# StairLed.net
KiCad netlist of a schematic drawn in Altium Designer
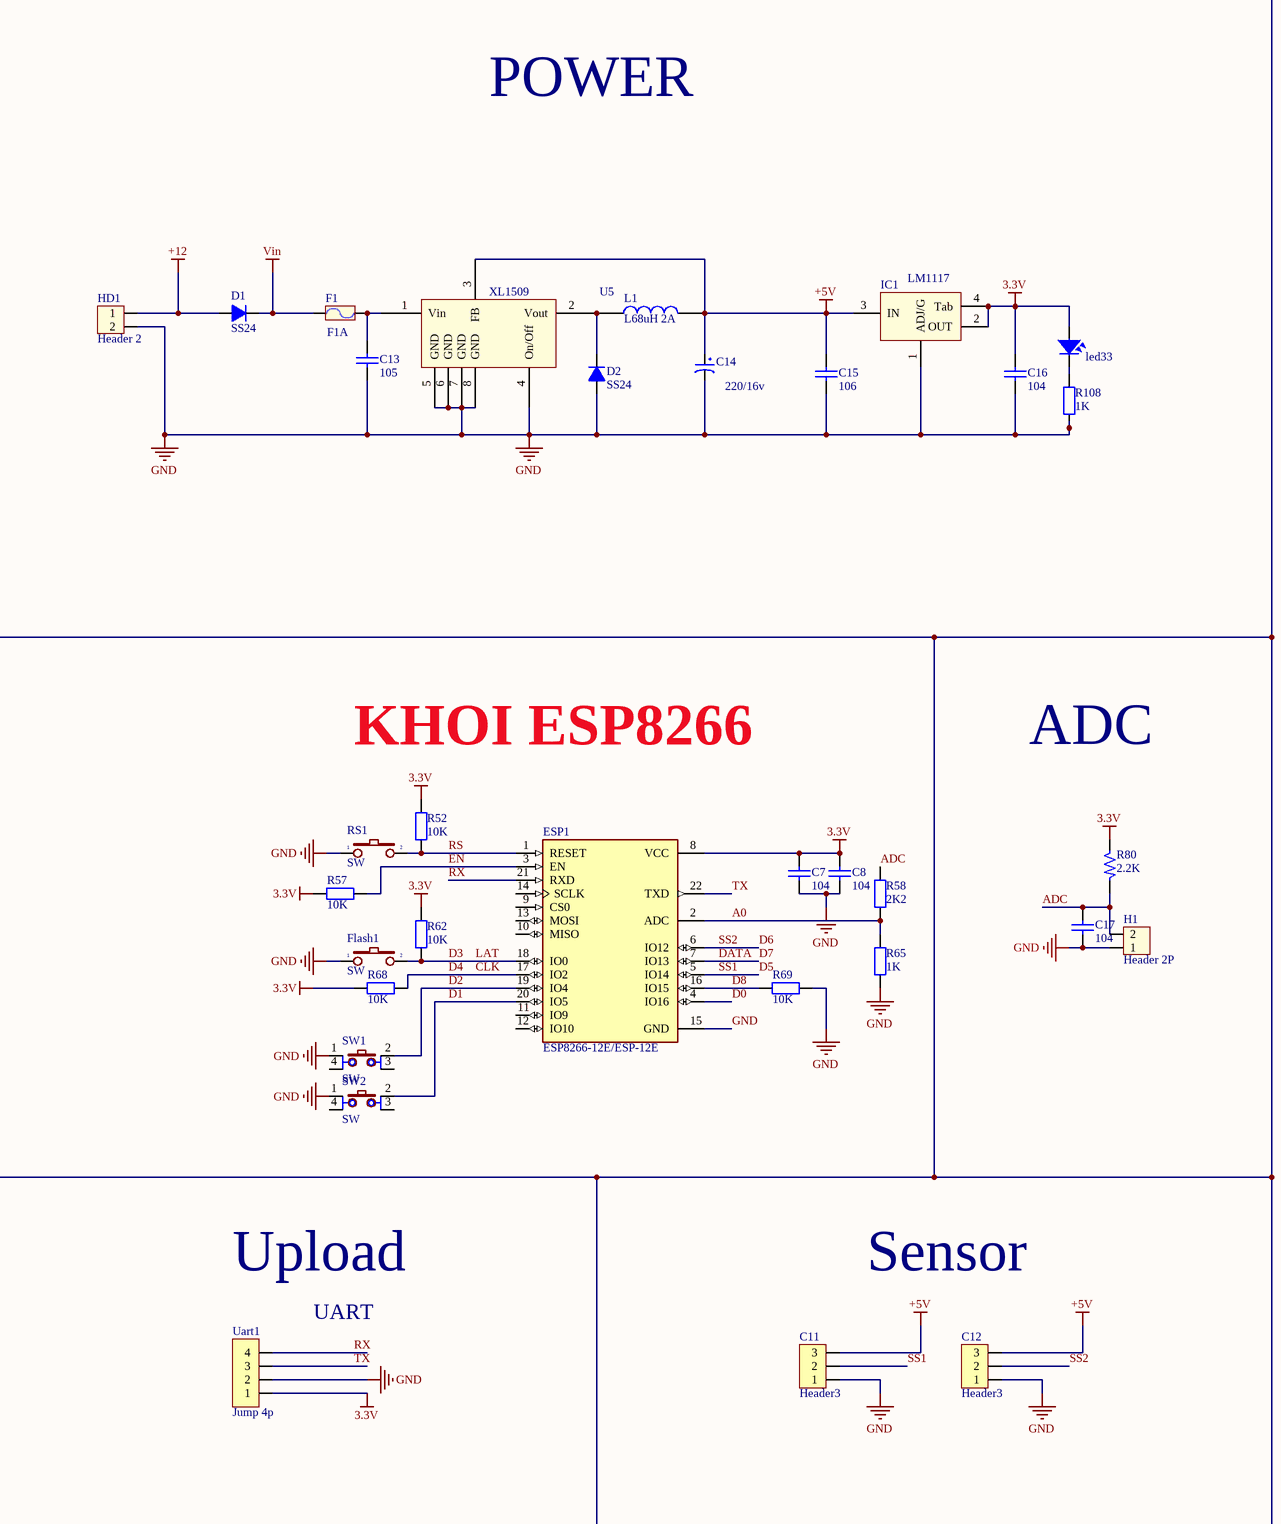
[diagram p0: StairLed.SchDoc, left]
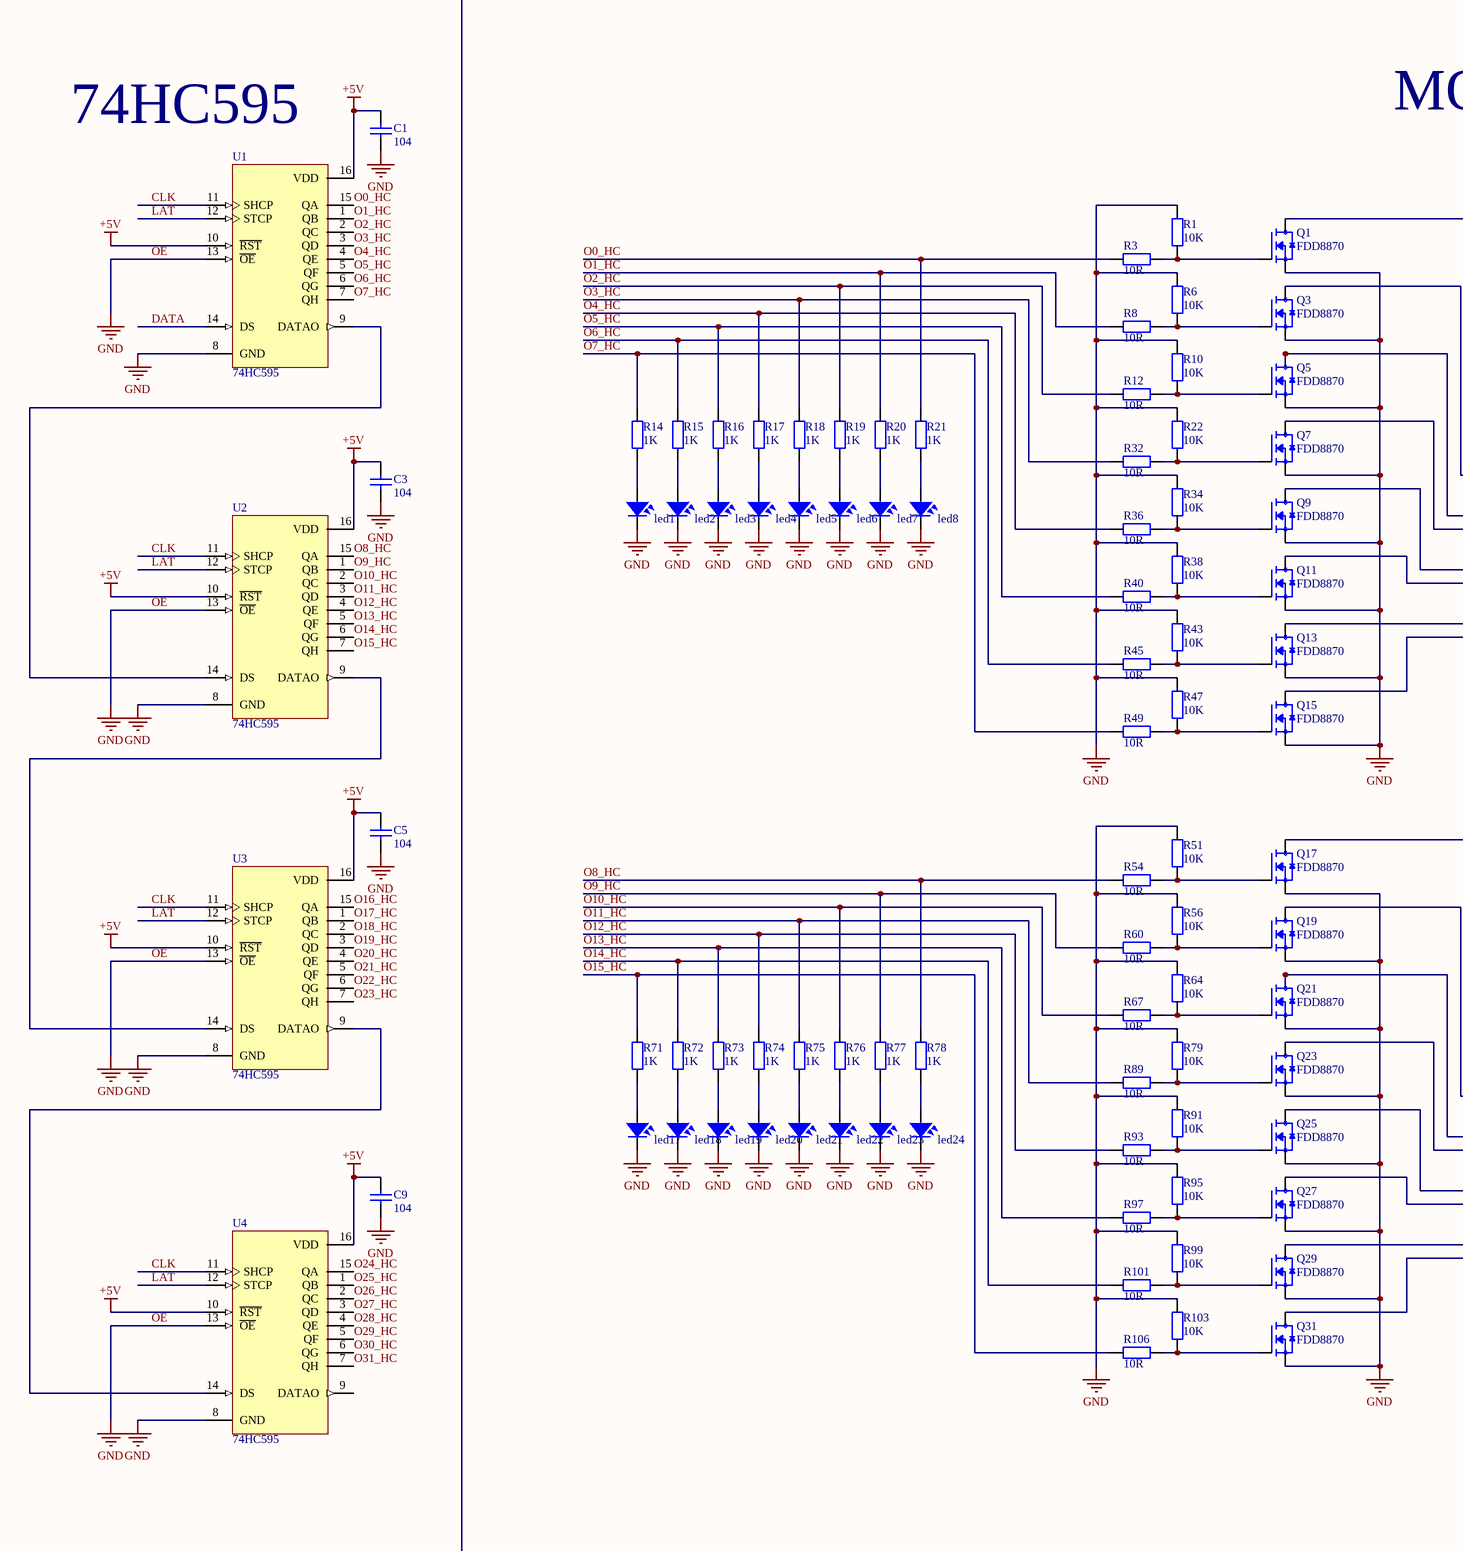
[diagram p1: StairLed.SchDoc, middle]
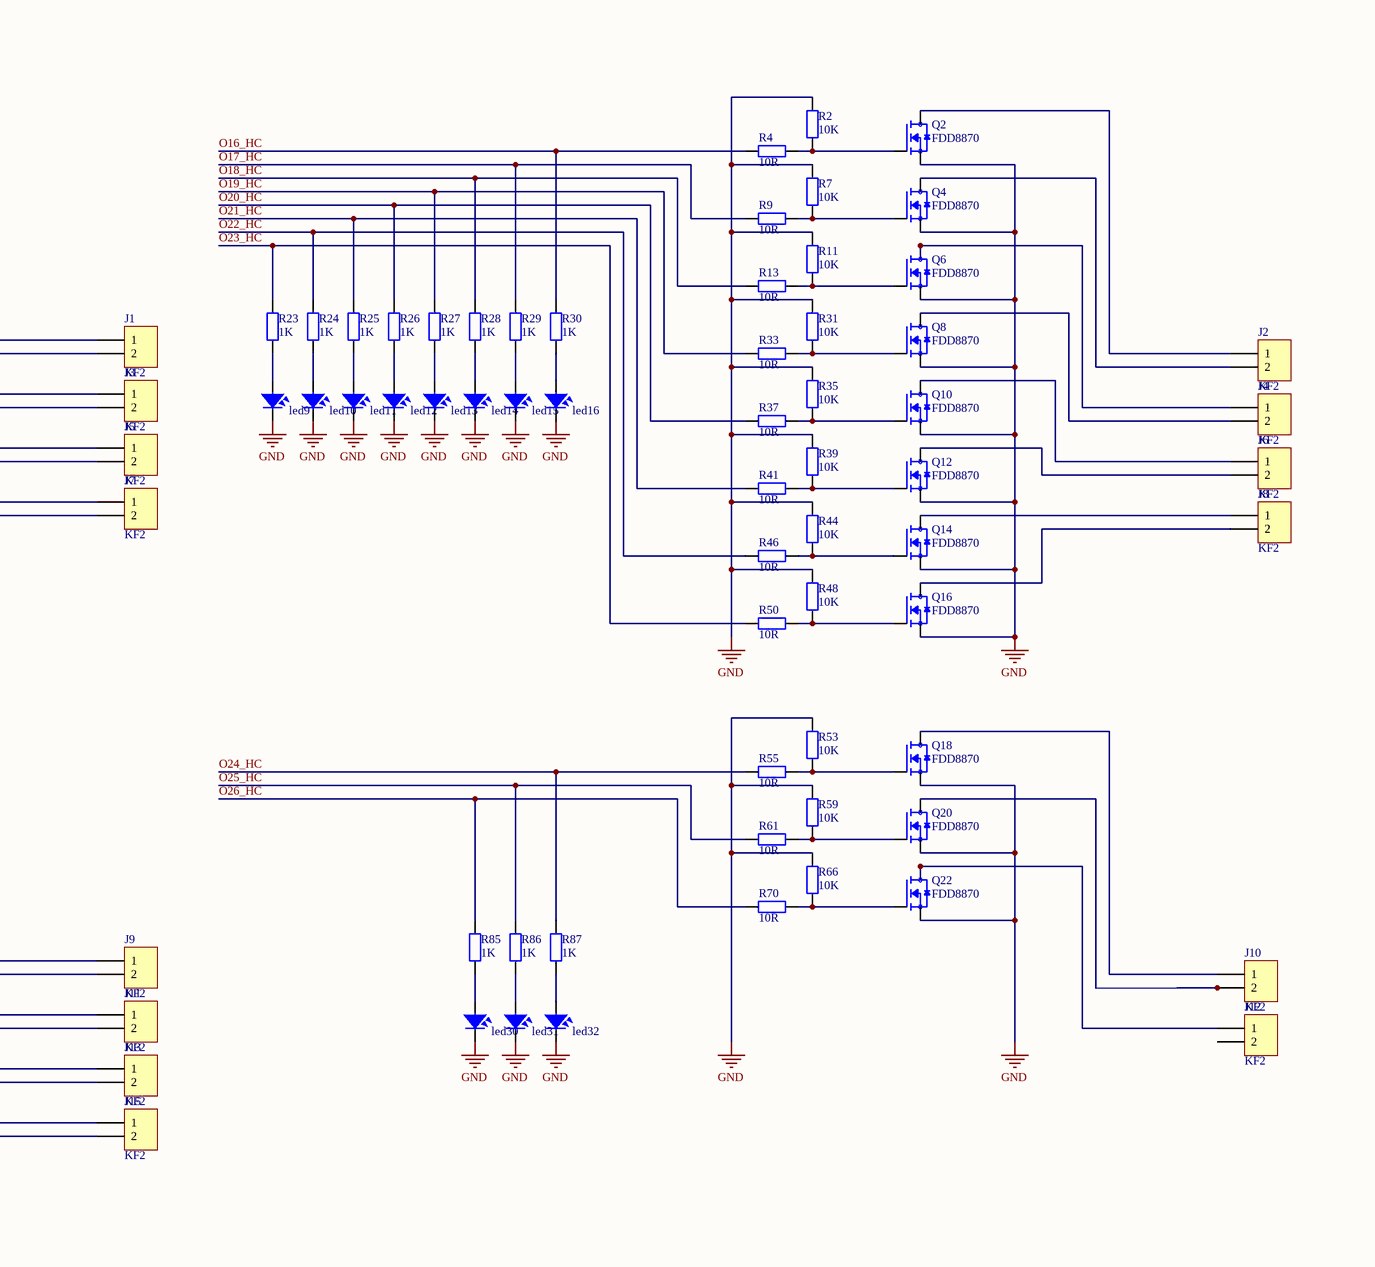
[diagram p2: StairLed.SchDoc, right]

(export (version "E")
  (design (tool "Eeschema 10.0.6"))
  (components
    (comp (ref "C1")
      (value "104")
      (footprint "Cap-0805")
      (libsource (lib "TDX_Local_LIbrary") (part "Cap-0805"))
    )
    (comp (ref "C3")
      (value "104")
      (footprint "Cap-0805")
      (libsource (lib "TDX_Local_LIbrary") (part "Cap-0805"))
    )
    (comp (ref "C5")
      (value "104")
      (footprint "Cap-0805")
      (libsource (lib "TDX_Local_LIbrary") (part "Cap-0805"))
    )
    (comp (ref "C7")
      (value "104")
      (footprint "Cap-0805")
      (description "Capacitor")
      (fields (field (name "PUBLISHER") "Altium Limited"))
      (libsource (lib "*") (part "Cap"))
    )
    (comp (ref "C8")
      (value "104")
      (footprint "Cap-0805")
      (description "Capacitor")
      (fields (field (name "PUBLISHER") "Altium Limited"))
      (libsource (lib "*") (part "Cap"))
    )
    (comp (ref "C9")
      (value "104")
      (footprint "Cap-0805")
      (libsource (lib "TDX_Local_LIbrary") (part "Cap-0805"))
    )
    (comp (ref "C11")
      (value "Header3")
      (footprint "Header3")
      (description "Header IDC, 3 x 1 Pin Vertical 2.54mm Pitch (Non-Boxed, Male)")
      (fields
        (field (name "MANUFACTURER") "Würth Elektronik eiSos GmbH")
        (field (name "PARTNO") "613002143121")
        (field (name "CREATED BY") "Karrer Zheng")
      )
      (libsource (lib "TechMT.VN_Lib_Project v2") (part "Header3"))
    )
    (comp (ref "C12")
      (value "Header3")
      (footprint "Header3")
      (description "Header IDC, 3 x 1 Pin Vertical 2.54mm Pitch (Non-Boxed, Male)")
      (fields
        (field (name "MANUFACTURER") "Würth Elektronik eiSos GmbH")
        (field (name "PARTNO") "613002143121")
        (field (name "CREATED BY") "Karrer Zheng")
      )
      (libsource (lib "TechMT.VN_Lib_Project v2") (part "Header3"))
    )
    (comp (ref "C13")
      (value "105")
      (footprint "Cap-0805")
      (description "Capacitor")
      (fields (field (name "PUBLISHER") "Altium Limited"))
      (libsource (lib "*") (part "Cap"))
    )
    (comp (ref "C14")
      (value "220/16v")
      (footprint "CAP-ALU-SMD-6.3x7.7x2.2")
      (description "T? Nhôm 330uF 50V 10x10.5MM")
      (libsource (lib "thuvien") (part "CP4"))
    )
    (comp (ref "C15")
      (value "106")
      (footprint "Cap-0805")
      (description "Capacitor")
      (fields (field (name "PUBLISHER") "Altium Limited"))
      (libsource (lib "*") (part "Cap"))
    )
    (comp (ref "C16")
      (value "104")
      (footprint "Cap-0805")
      (description "Capacitor")
      (fields (field (name "PUBLISHER") "Altium Limited"))
      (libsource (lib "*") (part "Cap"))
    )
    (comp (ref "C17")
      (value "104")
      (footprint "Cap-0805")
      (libsource (lib "TDX_Local_LIbrary") (part "Cap-0805"))
    )
    (comp (ref "D1")
      (value "SS24")
      (footprint "DO-214AC-Zenner")
      (description "Diode 1A")
      (libsource (lib "thuvien") (part "D1A"))
    )
    (comp (ref "D2")
      (value "SS24")
      (footprint "DO-214AC-Zenner")
      (description "Diode 1A")
      (libsource (lib "thuvien") (part "D1A"))
    )
    (comp (ref "ESP1")
      (value "ESP8266-12E/ESP-12E")
      (footprint "XCVR_ESP8266-12E/ESP-12E")
      (fields (field (name "MF") "AI-Thinker"))
      (libsource (lib "ESP8266-12E_ESP-12E (1)") (part "ESP8266-12E/ESP-12E"))
    )
    (comp (ref "F1")
      (value "F1A")
      (footprint "1812")
      (description "C?u chì t? ph?c h?i 1812 0.5A 30V MSMD050-30V")
      (fields (field (name "DESIGNED BY") "VanDungEvn"))
      (libsource (lib "syhaunguyen") (part "Fuse"))
    )
    (comp (ref "Flash1")
      (value "SW")
      (footprint "SW1-SMD")
      (description "Switch button 2 pin")
      (libsource (lib "TechMT.VN_Lib_Project v2") (part "SW2"))
    )
    (comp (ref "H1")
      (value "Header 2P")
      (footprint "Header 2P-T")
      (libsource (lib "TDX_Local_LIbrary") (part "Header 2P"))
    )
    (comp (ref "HD1")
      (value "Header 2")
      (footprint "HED2")
      (description "Header 2 (Green)")
      (libsource (lib "My library altium") (part "Header 2"))
    )
    (comp (ref "IC1")
      (value "LM1117")
      (footprint "SOT223-4N")
      (description "AMS1117-3.3V SOT223")
      (libsource (lib "thuvien") (part "LM1117"))
    )
    (comp (ref "J1")
      (value "KF2")
      (footprint "KF2-3.5")
      (fields
        (field (name "MANUFACTURER") "Würth Elektronik eiSos GmbH")
        (field (name "PARTNO") "691103110002")
        (field (name "CREATED BY") "Karrer Zheng")
      )
      (libsource (lib "TechMT.VN_Lib_Project v2") (part "KF2"))
    )
    (comp (ref "J2")
      (value "KF2")
      (footprint "KF2-3.5")
      (fields
        (field (name "MANUFACTURER") "Würth Elektronik eiSos GmbH")
        (field (name "PARTNO") "691103110002")
        (field (name "CREATED BY") "Karrer Zheng")
      )
      (libsource (lib "TechMT.VN_Lib_Project v2") (part "KF2"))
    )
    (comp (ref "J3")
      (value "KF2")
      (footprint "KF2-3.5")
      (fields
        (field (name "MANUFACTURER") "Würth Elektronik eiSos GmbH")
        (field (name "PARTNO") "691103110002")
        (field (name "CREATED BY") "Karrer Zheng")
      )
      (libsource (lib "TechMT.VN_Lib_Project v2") (part "KF2"))
    )
    (comp (ref "J4")
      (value "KF2")
      (footprint "KF2-3.5")
      (fields
        (field (name "MANUFACTURER") "Würth Elektronik eiSos GmbH")
        (field (name "PARTNO") "691103110002")
        (field (name "CREATED BY") "Karrer Zheng")
      )
      (libsource (lib "TechMT.VN_Lib_Project v2") (part "KF2"))
    )
    (comp (ref "J5")
      (value "KF2")
      (footprint "KF2-3.5")
      (fields
        (field (name "MANUFACTURER") "Würth Elektronik eiSos GmbH")
        (field (name "PARTNO") "691103110002")
        (field (name "CREATED BY") "Karrer Zheng")
      )
      (libsource (lib "TechMT.VN_Lib_Project v2") (part "KF2"))
    )
    (comp (ref "J6")
      (value "KF2")
      (footprint "KF2-3.5")
      (fields
        (field (name "MANUFACTURER") "Würth Elektronik eiSos GmbH")
        (field (name "PARTNO") "691103110002")
        (field (name "CREATED BY") "Karrer Zheng")
      )
      (libsource (lib "TechMT.VN_Lib_Project v2") (part "KF2"))
    )
    (comp (ref "J7")
      (value "KF2")
      (footprint "KF2-3.5")
      (fields
        (field (name "MANUFACTURER") "Würth Elektronik eiSos GmbH")
        (field (name "PARTNO") "691103110002")
        (field (name "CREATED BY") "Karrer Zheng")
      )
      (libsource (lib "TechMT.VN_Lib_Project v2") (part "KF2"))
    )
    (comp (ref "J8")
      (value "KF2")
      (footprint "KF2-3.5")
      (fields
        (field (name "MANUFACTURER") "Würth Elektronik eiSos GmbH")
        (field (name "PARTNO") "691103110002")
        (field (name "CREATED BY") "Karrer Zheng")
      )
      (libsource (lib "TechMT.VN_Lib_Project v2") (part "KF2"))
    )
    (comp (ref "J9")
      (value "KF2")
      (footprint "KF2-3.5")
      (fields
        (field (name "MANUFACTURER") "Würth Elektronik eiSos GmbH")
        (field (name "PARTNO") "691103110002")
        (field (name "CREATED BY") "Karrer Zheng")
      )
      (libsource (lib "TechMT.VN_Lib_Project v2") (part "KF2"))
    )
    (comp (ref "J10")
      (value "KF2")
      (footprint "KF2-3.5")
      (fields
        (field (name "MANUFACTURER") "Würth Elektronik eiSos GmbH")
        (field (name "PARTNO") "691103110002")
        (field (name "CREATED BY") "Karrer Zheng")
      )
      (libsource (lib "TechMT.VN_Lib_Project v2") (part "KF2"))
    )
    (comp (ref "J11")
      (value "KF2")
      (footprint "KF2-3.5")
      (fields
        (field (name "MANUFACTURER") "Würth Elektronik eiSos GmbH")
        (field (name "PARTNO") "691103110002")
        (field (name "CREATED BY") "Karrer Zheng")
      )
      (libsource (lib "TechMT.VN_Lib_Project v2") (part "KF2"))
    )
    (comp (ref "J12")
      (value "KF2")
      (footprint "KF2-3.5")
      (fields
        (field (name "MANUFACTURER") "Würth Elektronik eiSos GmbH")
        (field (name "PARTNO") "691103110002")
        (field (name "CREATED BY") "Karrer Zheng")
      )
      (libsource (lib "TechMT.VN_Lib_Project v2") (part "KF2"))
    )
    (comp (ref "J13")
      (value "KF2")
      (footprint "KF2-3.5")
      (fields
        (field (name "MANUFACTURER") "Würth Elektronik eiSos GmbH")
        (field (name "PARTNO") "691103110002")
        (field (name "CREATED BY") "Karrer Zheng")
      )
      (libsource (lib "TechMT.VN_Lib_Project v2") (part "KF2"))
    )
    (comp (ref "J15")
      (value "KF2")
      (footprint "KF2-3.5")
      (fields
        (field (name "MANUFACTURER") "Würth Elektronik eiSos GmbH")
        (field (name "PARTNO") "691103110002")
        (field (name "CREATED BY") "Karrer Zheng")
      )
      (libsource (lib "TechMT.VN_Lib_Project v2") (part "KF2"))
    )
    (comp (ref "L1")
      (value "L68uH 2A")
      (footprint "5D28")
      (description "Cu?n c?m dán CD74 68uH 7.4x7.4x4mm")
      (libsource (lib "*") (part "INDUCTOR"))
    )
    (comp (ref "led1")
      (value "LED SMD")
      (footprint "SM-LED-0805-Blue")
      (libsource (lib "syhaunguyen") (part "LED-SMD-0805"))
    )
    (comp (ref "led2")
      (value "LED SMD")
      (footprint "SM-LED-0805-Blue")
      (libsource (lib "syhaunguyen") (part "LED-SMD-0805"))
    )
    (comp (ref "led3")
      (value "LED SMD")
      (footprint "SM-LED-0805-Blue")
      (libsource (lib "syhaunguyen") (part "LED-SMD-0805"))
    )
    (comp (ref "led4")
      (value "LED SMD")
      (footprint "SM-LED-0805-Blue")
      (libsource (lib "syhaunguyen") (part "LED-SMD-0805"))
    )
    (comp (ref "led5")
      (value "LED SMD")
      (footprint "SM-LED-0805-Blue")
      (libsource (lib "syhaunguyen") (part "LED-SMD-0805"))
    )
    (comp (ref "led6")
      (value "LED SMD")
      (footprint "SM-LED-0805-Blue")
      (libsource (lib "syhaunguyen") (part "LED-SMD-0805"))
    )
    (comp (ref "led7")
      (value "LED SMD")
      (footprint "SM-LED-0805-Blue")
      (libsource (lib "syhaunguyen") (part "LED-SMD-0805"))
    )
    (comp (ref "led8")
      (value "LED SMD")
      (footprint "SM-LED-0805-Blue")
      (libsource (lib "syhaunguyen") (part "LED-SMD-0805"))
    )
    (comp (ref "led9")
      (value "LED SMD")
      (footprint "SM-LED-0805-Blue")
      (libsource (lib "syhaunguyen") (part "LED-SMD-0805"))
    )
    (comp (ref "led10")
      (value "LED SMD")
      (footprint "SM-LED-0805-Blue")
      (libsource (lib "syhaunguyen") (part "LED-SMD-0805"))
    )
    (comp (ref "led11")
      (value "LED SMD")
      (footprint "SM-LED-0805-Blue")
      (libsource (lib "syhaunguyen") (part "LED-SMD-0805"))
    )
    (comp (ref "led12")
      (value "LED SMD")
      (footprint "SM-LED-0805-Blue")
      (libsource (lib "syhaunguyen") (part "LED-SMD-0805"))
    )
    (comp (ref "led13")
      (value "LED SMD")
      (footprint "SM-LED-0805-Blue")
      (libsource (lib "syhaunguyen") (part "LED-SMD-0805"))
    )
    (comp (ref "led14")
      (value "LED SMD")
      (footprint "SM-LED-0805-Blue")
      (libsource (lib "syhaunguyen") (part "LED-SMD-0805"))
    )
    (comp (ref "led15")
      (value "LED SMD")
      (footprint "SM-LED-0805-Blue")
      (libsource (lib "syhaunguyen") (part "LED-SMD-0805"))
    )
    (comp (ref "led16")
      (value "LED SMD")
      (footprint "SM-LED-0805-Blue")
      (libsource (lib "syhaunguyen") (part "LED-SMD-0805"))
    )
    (comp (ref "led17")
      (value "LED SMD")
      (footprint "SM-LED-0805-Blue")
      (libsource (lib "syhaunguyen") (part "LED-SMD-0805"))
    )
    (comp (ref "led18")
      (value "LED SMD")
      (footprint "SM-LED-0805-Blue")
      (libsource (lib "syhaunguyen") (part "LED-SMD-0805"))
    )
    (comp (ref "led19")
      (value "LED SMD")
      (footprint "SM-LED-0805-Blue")
      (libsource (lib "syhaunguyen") (part "LED-SMD-0805"))
    )
    (comp (ref "led20")
      (value "LED SMD")
      (footprint "SM-LED-0805-Blue")
      (libsource (lib "syhaunguyen") (part "LED-SMD-0805"))
    )
    (comp (ref "led21")
      (value "LED SMD")
      (footprint "SM-LED-0805-Blue")
      (libsource (lib "syhaunguyen") (part "LED-SMD-0805"))
    )
    (comp (ref "led22")
      (value "LED SMD")
      (footprint "SM-LED-0805-Blue")
      (libsource (lib "syhaunguyen") (part "LED-SMD-0805"))
    )
    (comp (ref "led23")
      (value "LED SMD")
      (footprint "SM-LED-0805-Blue")
      (libsource (lib "syhaunguyen") (part "LED-SMD-0805"))
    )
    (comp (ref "led24")
      (value "LED SMD")
      (footprint "SM-LED-0805-Blue")
      (libsource (lib "syhaunguyen") (part "LED-SMD-0805"))
    )
    (comp (ref "led30")
      (value "LED SMD")
      (footprint "SM-LED-0805-Blue")
      (libsource (lib "syhaunguyen") (part "LED-SMD-0805"))
    )
    (comp (ref "led31")
      (value "LED SMD")
      (footprint "SM-LED-0805-Blue")
      (libsource (lib "syhaunguyen") (part "LED-SMD-0805"))
    )
    (comp (ref "led32")
      (value "LED SMD")
      (footprint "SM-LED-0805-Blue")
      (libsource (lib "syhaunguyen") (part "LED-SMD-0805"))
    )
    (comp (ref "led33")
      (value "LED SMD")
      (footprint "SM-LED-0805-Blue")
      (libsource (lib "syhaunguyen") (part "LED-SMD-0805"))
    )
    (comp (ref "Q1")
      (value "FDD8870")
      (footprint "TRANS_SQD50N03-06P-GE3")
      (fields (field (name "MP") "SQD50N03-06P-GE3"))
      (libsource (lib "SQD50N03-06P-GE3") (part "SQD50N03-06P-GE3"))
    )
    (comp (ref "Q2")
      (value "FDD8870")
      (footprint "TRANS_SQD50N03-06P-GE3")
      (fields (field (name "MP") "SQD50N03-06P-GE3"))
      (libsource (lib "SQD50N03-06P-GE3") (part "SQD50N03-06P-GE3"))
    )
    (comp (ref "Q3")
      (value "FDD8870")
      (footprint "TRANS_SQD50N03-06P-GE3")
      (fields (field (name "MP") "SQD50N03-06P-GE3"))
      (libsource (lib "SQD50N03-06P-GE3") (part "SQD50N03-06P-GE3"))
    )
    (comp (ref "Q4")
      (value "FDD8870")
      (footprint "TRANS_SQD50N03-06P-GE3")
      (fields (field (name "MP") "SQD50N03-06P-GE3"))
      (libsource (lib "SQD50N03-06P-GE3") (part "SQD50N03-06P-GE3"))
    )
    (comp (ref "Q5")
      (value "FDD8870")
      (footprint "TRANS_SQD50N03-06P-GE3")
      (fields (field (name "MP") "SQD50N03-06P-GE3"))
      (libsource (lib "SQD50N03-06P-GE3") (part "SQD50N03-06P-GE3"))
    )
    (comp (ref "Q6")
      (value "FDD8870")
      (footprint "TRANS_SQD50N03-06P-GE3")
      (fields (field (name "MP") "SQD50N03-06P-GE3"))
      (libsource (lib "SQD50N03-06P-GE3") (part "SQD50N03-06P-GE3"))
    )
    (comp (ref "Q7")
      (value "FDD8870")
      (footprint "TRANS_SQD50N03-06P-GE3")
      (fields (field (name "MP") "SQD50N03-06P-GE3"))
      (libsource (lib "SQD50N03-06P-GE3") (part "SQD50N03-06P-GE3"))
    )
    (comp (ref "Q8")
      (value "FDD8870")
      (footprint "TRANS_SQD50N03-06P-GE3")
      (fields (field (name "MP") "SQD50N03-06P-GE3"))
      (libsource (lib "SQD50N03-06P-GE3") (part "SQD50N03-06P-GE3"))
    )
    (comp (ref "Q9")
      (value "FDD8870")
      (footprint "TRANS_SQD50N03-06P-GE3")
      (fields (field (name "MP") "SQD50N03-06P-GE3"))
      (libsource (lib "SQD50N03-06P-GE3") (part "SQD50N03-06P-GE3"))
    )
    (comp (ref "Q10")
      (value "FDD8870")
      (footprint "TRANS_SQD50N03-06P-GE3")
      (fields (field (name "MP") "SQD50N03-06P-GE3"))
      (libsource (lib "SQD50N03-06P-GE3") (part "SQD50N03-06P-GE3"))
    )
    (comp (ref "Q11")
      (value "FDD8870")
      (footprint "TRANS_SQD50N03-06P-GE3")
      (fields (field (name "MP") "SQD50N03-06P-GE3"))
      (libsource (lib "SQD50N03-06P-GE3") (part "SQD50N03-06P-GE3"))
    )
    (comp (ref "Q12")
      (value "FDD8870")
      (footprint "TRANS_SQD50N03-06P-GE3")
      (fields (field (name "MP") "SQD50N03-06P-GE3"))
      (libsource (lib "SQD50N03-06P-GE3") (part "SQD50N03-06P-GE3"))
    )
    (comp (ref "Q13")
      (value "FDD8870")
      (footprint "TRANS_SQD50N03-06P-GE3")
      (fields (field (name "MP") "SQD50N03-06P-GE3"))
      (libsource (lib "SQD50N03-06P-GE3") (part "SQD50N03-06P-GE3"))
    )
    (comp (ref "Q14")
      (value "FDD8870")
      (footprint "TRANS_SQD50N03-06P-GE3")
      (fields (field (name "MP") "SQD50N03-06P-GE3"))
      (libsource (lib "SQD50N03-06P-GE3") (part "SQD50N03-06P-GE3"))
    )
    (comp (ref "Q15")
      (value "FDD8870")
      (footprint "TRANS_SQD50N03-06P-GE3")
      (fields (field (name "MP") "SQD50N03-06P-GE3"))
      (libsource (lib "SQD50N03-06P-GE3") (part "SQD50N03-06P-GE3"))
    )
    (comp (ref "Q16")
      (value "FDD8870")
      (footprint "TRANS_SQD50N03-06P-GE3")
      (fields (field (name "MP") "SQD50N03-06P-GE3"))
      (libsource (lib "SQD50N03-06P-GE3") (part "SQD50N03-06P-GE3"))
    )
    (comp (ref "Q17")
      (value "FDD8870")
      (footprint "TRANS_SQD50N03-06P-GE3")
      (fields (field (name "MP") "SQD50N03-06P-GE3"))
      (libsource (lib "SQD50N03-06P-GE3") (part "SQD50N03-06P-GE3"))
    )
    (comp (ref "Q18")
      (value "FDD8870")
      (footprint "TRANS_SQD50N03-06P-GE3")
      (fields (field (name "MP") "SQD50N03-06P-GE3"))
      (libsource (lib "SQD50N03-06P-GE3") (part "SQD50N03-06P-GE3"))
    )
    (comp (ref "Q19")
      (value "FDD8870")
      (footprint "TRANS_SQD50N03-06P-GE3")
      (fields (field (name "MP") "SQD50N03-06P-GE3"))
      (libsource (lib "SQD50N03-06P-GE3") (part "SQD50N03-06P-GE3"))
    )
    (comp (ref "Q20")
      (value "FDD8870")
      (footprint "TRANS_SQD50N03-06P-GE3")
      (fields (field (name "MP") "SQD50N03-06P-GE3"))
      (libsource (lib "SQD50N03-06P-GE3") (part "SQD50N03-06P-GE3"))
    )
    (comp (ref "Q21")
      (value "FDD8870")
      (footprint "TRANS_SQD50N03-06P-GE3")
      (fields (field (name "MP") "SQD50N03-06P-GE3"))
      (libsource (lib "SQD50N03-06P-GE3") (part "SQD50N03-06P-GE3"))
    )
    (comp (ref "Q22")
      (value "FDD8870")
      (footprint "TRANS_SQD50N03-06P-GE3")
      (fields (field (name "MP") "SQD50N03-06P-GE3"))
      (libsource (lib "SQD50N03-06P-GE3") (part "SQD50N03-06P-GE3"))
    )
    (comp (ref "Q23")
      (value "FDD8870")
      (footprint "TRANS_SQD50N03-06P-GE3")
      (fields (field (name "MP") "SQD50N03-06P-GE3"))
      (libsource (lib "SQD50N03-06P-GE3") (part "SQD50N03-06P-GE3"))
    )
    (comp (ref "Q25")
      (value "FDD8870")
      (footprint "TRANS_SQD50N03-06P-GE3")
      (fields (field (name "MP") "SQD50N03-06P-GE3"))
      (libsource (lib "SQD50N03-06P-GE3") (part "SQD50N03-06P-GE3"))
    )
    (comp (ref "Q27")
      (value "FDD8870")
      (footprint "TRANS_SQD50N03-06P-GE3")
      (fields (field (name "MP") "SQD50N03-06P-GE3"))
      (libsource (lib "SQD50N03-06P-GE3") (part "SQD50N03-06P-GE3"))
    )
    (comp (ref "Q29")
      (value "FDD8870")
      (footprint "TRANS_SQD50N03-06P-GE3")
      (fields (field (name "MP") "SQD50N03-06P-GE3"))
      (libsource (lib "SQD50N03-06P-GE3") (part "SQD50N03-06P-GE3"))
    )
    (comp (ref "Q31")
      (value "FDD8870")
      (footprint "TRANS_SQD50N03-06P-GE3")
      (fields (field (name "MP") "SQD50N03-06P-GE3"))
      (libsource (lib "SQD50N03-06P-GE3") (part "SQD50N03-06P-GE3"))
    )
    (comp (ref "R1")
      (value "10K")
      (footprint "R0805")
      (description "Tr? 0805 1%")
      (fields (field (name "PUBLISHER") "Altium Limited"))
      (libsource (lib "") (part "RES_08_2"))
    )
    (comp (ref "R2")
      (value "10K")
      (footprint "R0805")
      (description "Tr? 0805 1%")
      (fields (field (name "PUBLISHER") "Altium Limited"))
      (libsource (lib "") (part "RES_08_2"))
    )
    (comp (ref "R3")
      (value "10R")
      (footprint "R0805")
      (description "Tr? 0805 1%")
      (fields (field (name "PUBLISHER") "Altium Limited"))
      (libsource (lib "Schematic") (part "RES_08"))
    )
    (comp (ref "R4")
      (value "10R")
      (footprint "R0805")
      (description "Tr? 0805 1%")
      (fields (field (name "PUBLISHER") "Altium Limited"))
      (libsource (lib "Schematic") (part "RES_08"))
    )
    (comp (ref "R6")
      (value "10K")
      (footprint "R0805")
      (description "Tr? 0805 1%")
      (fields (field (name "PUBLISHER") "Altium Limited"))
      (libsource (lib "") (part "RES_08_2"))
    )
    (comp (ref "R7")
      (value "10K")
      (footprint "R0805")
      (description "Tr? 0805 1%")
      (fields (field (name "PUBLISHER") "Altium Limited"))
      (libsource (lib "") (part "RES_08_2"))
    )
    (comp (ref "R8")
      (value "10R")
      (footprint "R0805")
      (description "Tr? 0805 1%")
      (fields (field (name "PUBLISHER") "Altium Limited"))
      (libsource (lib "Schematic") (part "RES_08"))
    )
    (comp (ref "R9")
      (value "10R")
      (footprint "R0805")
      (description "Tr? 0805 1%")
      (fields (field (name "PUBLISHER") "Altium Limited"))
      (libsource (lib "Schematic") (part "RES_08"))
    )
    (comp (ref "R10")
      (value "10K")
      (footprint "R0805")
      (description "Tr? 0805 1%")
      (fields (field (name "PUBLISHER") "Altium Limited"))
      (libsource (lib "") (part "RES_08_2"))
    )
    (comp (ref "R11")
      (value "10K")
      (footprint "R0805")
      (description "Tr? 0805 1%")
      (fields (field (name "PUBLISHER") "Altium Limited"))
      (libsource (lib "") (part "RES_08_2"))
    )
    (comp (ref "R12")
      (value "10R")
      (footprint "R0805")
      (description "Tr? 0805 1%")
      (fields (field (name "PUBLISHER") "Altium Limited"))
      (libsource (lib "Schematic") (part "RES_08"))
    )
    (comp (ref "R13")
      (value "10R")
      (footprint "R0805")
      (description "Tr? 0805 1%")
      (fields (field (name "PUBLISHER") "Altium Limited"))
      (libsource (lib "Schematic") (part "RES_08"))
    )
    (comp (ref "R14")
      (value "1K")
      (footprint "R0805")
      (description "Tr? 0805 1%")
      (fields (field (name "PUBLISHER") "Altium Limited"))
      (libsource (lib "") (part "RES_08_1"))
    )
    (comp (ref "R15")
      (value "1K")
      (footprint "R0805")
      (description "Tr? 0805 1%")
      (fields (field (name "PUBLISHER") "Altium Limited"))
      (libsource (lib "") (part "RES_08_1"))
    )
    (comp (ref "R16")
      (value "1K")
      (footprint "R0805")
      (description "Tr? 0805 1%")
      (fields (field (name "PUBLISHER") "Altium Limited"))
      (libsource (lib "") (part "RES_08_1"))
    )
    (comp (ref "R17")
      (value "1K")
      (footprint "R0805")
      (description "Tr? 0805 1%")
      (fields (field (name "PUBLISHER") "Altium Limited"))
      (libsource (lib "") (part "RES_08_1"))
    )
    (comp (ref "R18")
      (value "1K")
      (footprint "R0805")
      (description "Tr? 0805 1%")
      (fields (field (name "PUBLISHER") "Altium Limited"))
      (libsource (lib "") (part "RES_08_1"))
    )
    (comp (ref "R19")
      (value "1K")
      (footprint "R0805")
      (description "Tr? 0805 1%")
      (fields (field (name "PUBLISHER") "Altium Limited"))
      (libsource (lib "") (part "RES_08_1"))
    )
    (comp (ref "R20")
      (value "1K")
      (footprint "R0805")
      (description "Tr? 0805 1%")
      (fields (field (name "PUBLISHER") "Altium Limited"))
      (libsource (lib "") (part "RES_08_1"))
    )
    (comp (ref "R21")
      (value "1K")
      (footprint "R0805")
      (description "Tr? 0805 1%")
      (fields (field (name "PUBLISHER") "Altium Limited"))
      (libsource (lib "") (part "RES_08_1"))
    )
    (comp (ref "R22")
      (value "10K")
      (footprint "R0805")
      (description "Tr? 0805 1%")
      (fields (field (name "PUBLISHER") "Altium Limited"))
      (libsource (lib "") (part "RES_08_2"))
    )
    (comp (ref "R23")
      (value "1K")
      (footprint "R0805")
      (description "Tr? 0805 1%")
      (fields (field (name "PUBLISHER") "Altium Limited"))
      (libsource (lib "") (part "RES_08_1"))
    )
    (comp (ref "R24")
      (value "1K")
      (footprint "R0805")
      (description "Tr? 0805 1%")
      (fields (field (name "PUBLISHER") "Altium Limited"))
      (libsource (lib "") (part "RES_08_1"))
    )
    (comp (ref "R25")
      (value "1K")
      (footprint "R0805")
      (description "Tr? 0805 1%")
      (fields (field (name "PUBLISHER") "Altium Limited"))
      (libsource (lib "") (part "RES_08_1"))
    )
    (comp (ref "R26")
      (value "1K")
      (footprint "R0805")
      (description "Tr? 0805 1%")
      (fields (field (name "PUBLISHER") "Altium Limited"))
      (libsource (lib "") (part "RES_08_1"))
    )
    (comp (ref "R27")
      (value "1K")
      (footprint "R0805")
      (description "Tr? 0805 1%")
      (fields (field (name "PUBLISHER") "Altium Limited"))
      (libsource (lib "") (part "RES_08_1"))
    )
    (comp (ref "R28")
      (value "1K")
      (footprint "R0805")
      (description "Tr? 0805 1%")
      (fields (field (name "PUBLISHER") "Altium Limited"))
      (libsource (lib "") (part "RES_08_1"))
    )
    (comp (ref "R29")
      (value "1K")
      (footprint "R0805")
      (description "Tr? 0805 1%")
      (fields (field (name "PUBLISHER") "Altium Limited"))
      (libsource (lib "") (part "RES_08_1"))
    )
    (comp (ref "R30")
      (value "1K")
      (footprint "R0805")
      (description "Tr? 0805 1%")
      (fields (field (name "PUBLISHER") "Altium Limited"))
      (libsource (lib "") (part "RES_08_1"))
    )
    (comp (ref "R31")
      (value "10K")
      (footprint "R0805")
      (description "Tr? 0805 1%")
      (fields (field (name "PUBLISHER") "Altium Limited"))
      (libsource (lib "") (part "RES_08_2"))
    )
    (comp (ref "R32")
      (value "10R")
      (footprint "R0805")
      (description "Tr? 0805 1%")
      (fields (field (name "PUBLISHER") "Altium Limited"))
      (libsource (lib "Schematic") (part "RES_08"))
    )
    (comp (ref "R33")
      (value "10R")
      (footprint "R0805")
      (description "Tr? 0805 1%")
      (fields (field (name "PUBLISHER") "Altium Limited"))
      (libsource (lib "Schematic") (part "RES_08"))
    )
    (comp (ref "R34")
      (value "10K")
      (footprint "R0805")
      (description "Tr? 0805 1%")
      (fields (field (name "PUBLISHER") "Altium Limited"))
      (libsource (lib "") (part "RES_08_2"))
    )
    (comp (ref "R35")
      (value "10K")
      (footprint "R0805")
      (description "Tr? 0805 1%")
      (fields (field (name "PUBLISHER") "Altium Limited"))
      (libsource (lib "") (part "RES_08_2"))
    )
    (comp (ref "R36")
      (value "10R")
      (footprint "R0805")
      (description "Tr? 0805 1%")
      (fields (field (name "PUBLISHER") "Altium Limited"))
      (libsource (lib "Schematic") (part "RES_08"))
    )
    (comp (ref "R37")
      (value "10R")
      (footprint "R0805")
      (description "Tr? 0805 1%")
      (fields (field (name "PUBLISHER") "Altium Limited"))
      (libsource (lib "Schematic") (part "RES_08"))
    )
    (comp (ref "R38")
      (value "10K")
      (footprint "R0805")
      (description "Tr? 0805 1%")
      (fields (field (name "PUBLISHER") "Altium Limited"))
      (libsource (lib "") (part "RES_08_2"))
    )
    (comp (ref "R39")
      (value "10K")
      (footprint "R0805")
      (description "Tr? 0805 1%")
      (fields (field (name "PUBLISHER") "Altium Limited"))
      (libsource (lib "") (part "RES_08_2"))
    )
    (comp (ref "R40")
      (value "10R")
      (footprint "R0805")
      (description "Tr? 0805 1%")
      (fields (field (name "PUBLISHER") "Altium Limited"))
      (libsource (lib "Schematic") (part "RES_08"))
    )
    (comp (ref "R41")
      (value "10R")
      (footprint "R0805")
      (description "Tr? 0805 1%")
      (fields (field (name "PUBLISHER") "Altium Limited"))
      (libsource (lib "Schematic") (part "RES_08"))
    )
    (comp (ref "R43")
      (value "10K")
      (footprint "R0805")
      (description "Tr? 0805 1%")
      (fields (field (name "PUBLISHER") "Altium Limited"))
      (libsource (lib "") (part "RES_08_2"))
    )
    (comp (ref "R44")
      (value "10K")
      (footprint "R0805")
      (description "Tr? 0805 1%")
      (fields (field (name "PUBLISHER") "Altium Limited"))
      (libsource (lib "") (part "RES_08_2"))
    )
    (comp (ref "R45")
      (value "10R")
      (footprint "R0805")
      (description "Tr? 0805 1%")
      (fields (field (name "PUBLISHER") "Altium Limited"))
      (libsource (lib "Schematic") (part "RES_08"))
    )
    (comp (ref "R46")
      (value "10R")
      (footprint "R0805")
      (description "Tr? 0805 1%")
      (fields (field (name "PUBLISHER") "Altium Limited"))
      (libsource (lib "Schematic") (part "RES_08"))
    )
    (comp (ref "R47")
      (value "10K")
      (footprint "R0805")
      (description "Tr? 0805 1%")
      (fields (field (name "PUBLISHER") "Altium Limited"))
      (libsource (lib "") (part "RES_08_2"))
    )
    (comp (ref "R48")
      (value "10K")
      (footprint "R0805")
      (description "Tr? 0805 1%")
      (fields (field (name "PUBLISHER") "Altium Limited"))
      (libsource (lib "") (part "RES_08_2"))
    )
    (comp (ref "R49")
      (value "10R")
      (footprint "R0805")
      (description "Tr? 0805 1%")
      (fields (field (name "PUBLISHER") "Altium Limited"))
      (libsource (lib "Schematic") (part "RES_08"))
    )
    (comp (ref "R50")
      (value "10R")
      (footprint "R0805")
      (description "Tr? 0805 1%")
      (fields (field (name "PUBLISHER") "Altium Limited"))
      (libsource (lib "Schematic") (part "RES_08"))
    )
    (comp (ref "R51")
      (value "10K")
      (footprint "R0805")
      (description "Tr? 0805 1%")
      (fields (field (name "PUBLISHER") "Altium Limited"))
      (libsource (lib "") (part "RES_08_2"))
    )
    (comp (ref "R52")
      (value "10K")
      (footprint "R0805")
      (description "RES_08")
      (fields (field (name "PUBLISHER") "Altium Limited"))
      (libsource (lib "TransmitterMainBoard") (part "RES_08"))
    )
    (comp (ref "R53")
      (value "10K")
      (footprint "R0805")
      (description "Tr? 0805 1%")
      (fields (field (name "PUBLISHER") "Altium Limited"))
      (libsource (lib "") (part "RES_08_2"))
    )
    (comp (ref "R54")
      (value "10R")
      (footprint "R0805")
      (description "Tr? 0805 1%")
      (fields (field (name "PUBLISHER") "Altium Limited"))
      (libsource (lib "Schematic") (part "RES_08"))
    )
    (comp (ref "R55")
      (value "10R")
      (footprint "R0805")
      (description "Tr? 0805 1%")
      (fields (field (name "PUBLISHER") "Altium Limited"))
      (libsource (lib "Schematic") (part "RES_08"))
    )
    (comp (ref "R56")
      (value "10K")
      (footprint "R0805")
      (description "Tr? 0805 1%")
      (fields (field (name "PUBLISHER") "Altium Limited"))
      (libsource (lib "") (part "RES_08_2"))
    )
    (comp (ref "R57")
      (value "10K")
      (footprint "R0805")
      (description "RES_08")
      (fields (field (name "PUBLISHER") "Altium Limited"))
      (libsource (lib "") (part "RES_08_1"))
    )
    (comp (ref "R58")
      (value "2K2")
      (footprint "R0805")
      (description "Tr? 0805 1%")
      (fields (field (name "PUBLISHER") "Altium Limited"))
      (libsource (lib "") (part "RES_08_2"))
    )
    (comp (ref "R59")
      (value "10K")
      (footprint "R0805")
      (description "Tr? 0805 1%")
      (fields (field (name "PUBLISHER") "Altium Limited"))
      (libsource (lib "") (part "RES_08_2"))
    )
    (comp (ref "R60")
      (value "10R")
      (footprint "R0805")
      (description "Tr? 0805 1%")
      (fields (field (name "PUBLISHER") "Altium Limited"))
      (libsource (lib "Schematic") (part "RES_08"))
    )
    (comp (ref "R61")
      (value "10R")
      (footprint "R0805")
      (description "Tr? 0805 1%")
      (fields (field (name "PUBLISHER") "Altium Limited"))
      (libsource (lib "Schematic") (part "RES_08"))
    )
    (comp (ref "R62")
      (value "10K")
      (footprint "R0805")
      (description "RES_08")
      (fields (field (name "PUBLISHER") "Altium Limited"))
      (libsource (lib "TransmitterMainBoard") (part "RES_08"))
    )
    (comp (ref "R64")
      (value "10K")
      (footprint "R0805")
      (description "Tr? 0805 1%")
      (fields (field (name "PUBLISHER") "Altium Limited"))
      (libsource (lib "") (part "RES_08_2"))
    )
    (comp (ref "R65")
      (value "1K")
      (footprint "R0805")
      (description "Tr? 0805 1%")
      (fields (field (name "PUBLISHER") "Altium Limited"))
      (libsource (lib "") (part "RES_08_2"))
    )
    (comp (ref "R66")
      (value "10K")
      (footprint "R0805")
      (description "Tr? 0805 1%")
      (fields (field (name "PUBLISHER") "Altium Limited"))
      (libsource (lib "") (part "RES_08_2"))
    )
    (comp (ref "R67")
      (value "10R")
      (footprint "R0805")
      (description "Tr? 0805 1%")
      (fields (field (name "PUBLISHER") "Altium Limited"))
      (libsource (lib "Schematic") (part "RES_08"))
    )
    (comp (ref "R68")
      (value "10K")
      (footprint "R0805")
      (description "RES_08")
      (fields (field (name "PUBLISHER") "Altium Limited"))
      (libsource (lib "") (part "RES_08_1"))
    )
    (comp (ref "R69")
      (value "10K")
      (footprint "R0805")
      (description "RES_08")
      (fields (field (name "PUBLISHER") "Altium Limited"))
      (libsource (lib "") (part "RES_08_1"))
    )
    (comp (ref "R70")
      (value "10R")
      (footprint "R0805")
      (description "Tr? 0805 1%")
      (fields (field (name "PUBLISHER") "Altium Limited"))
      (libsource (lib "Schematic") (part "RES_08"))
    )
    (comp (ref "R71")
      (value "1K")
      (footprint "R0805")
      (description "Tr? 0805 1%")
      (fields (field (name "PUBLISHER") "Altium Limited"))
      (libsource (lib "") (part "RES_08_1"))
    )
    (comp (ref "R72")
      (value "1K")
      (footprint "R0805")
      (description "Tr? 0805 1%")
      (fields (field (name "PUBLISHER") "Altium Limited"))
      (libsource (lib "") (part "RES_08_1"))
    )
    (comp (ref "R73")
      (value "1K")
      (footprint "R0805")
      (description "Tr? 0805 1%")
      (fields (field (name "PUBLISHER") "Altium Limited"))
      (libsource (lib "") (part "RES_08_1"))
    )
    (comp (ref "R74")
      (value "1K")
      (footprint "R0805")
      (description "Tr? 0805 1%")
      (fields (field (name "PUBLISHER") "Altium Limited"))
      (libsource (lib "") (part "RES_08_1"))
    )
    (comp (ref "R75")
      (value "1K")
      (footprint "R0805")
      (description "Tr? 0805 1%")
      (fields (field (name "PUBLISHER") "Altium Limited"))
      (libsource (lib "") (part "RES_08_1"))
    )
    (comp (ref "R76")
      (value "1K")
      (footprint "R0805")
      (description "Tr? 0805 1%")
      (fields (field (name "PUBLISHER") "Altium Limited"))
      (libsource (lib "") (part "RES_08_1"))
    )
    (comp (ref "R77")
      (value "1K")
      (footprint "R0805")
      (description "Tr? 0805 1%")
      (fields (field (name "PUBLISHER") "Altium Limited"))
      (libsource (lib "") (part "RES_08_1"))
    )
    (comp (ref "R78")
      (value "1K")
      (footprint "R0805")
      (description "Tr? 0805 1%")
      (fields (field (name "PUBLISHER") "Altium Limited"))
      (libsource (lib "") (part "RES_08_1"))
    )
    (comp (ref "R79")
      (value "10K")
      (footprint "R0805")
      (description "Tr? 0805 1%")
      (fields (field (name "PUBLISHER") "Altium Limited"))
      (libsource (lib "") (part "RES_08_2"))
    )
    (comp (ref "R80")
      (value "2.2K")
      (footprint "Res-0805")
      (libsource (lib "TDX_Local_LIbrary") (part "Res-0805"))
    )
    (comp (ref "R85")
      (value "1K")
      (footprint "R0805")
      (description "Tr? 0805 1%")
      (fields (field (name "PUBLISHER") "Altium Limited"))
      (libsource (lib "") (part "RES_08_1"))
    )
    (comp (ref "R86")
      (value "1K")
      (footprint "R0805")
      (description "Tr? 0805 1%")
      (fields (field (name "PUBLISHER") "Altium Limited"))
      (libsource (lib "") (part "RES_08_1"))
    )
    (comp (ref "R87")
      (value "1K")
      (footprint "R0805")
      (description "Tr? 0805 1%")
      (fields (field (name "PUBLISHER") "Altium Limited"))
      (libsource (lib "") (part "RES_08_1"))
    )
    (comp (ref "R89")
      (value "10R")
      (footprint "R0805")
      (description "Tr? 0805 1%")
      (fields (field (name "PUBLISHER") "Altium Limited"))
      (libsource (lib "Schematic") (part "RES_08"))
    )
    (comp (ref "R91")
      (value "10K")
      (footprint "R0805")
      (description "Tr? 0805 1%")
      (fields (field (name "PUBLISHER") "Altium Limited"))
      (libsource (lib "") (part "RES_08_2"))
    )
    (comp (ref "R93")
      (value "10R")
      (footprint "R0805")
      (description "Tr? 0805 1%")
      (fields (field (name "PUBLISHER") "Altium Limited"))
      (libsource (lib "Schematic") (part "RES_08"))
    )
    (comp (ref "R95")
      (value "10K")
      (footprint "R0805")
      (description "Tr? 0805 1%")
      (fields (field (name "PUBLISHER") "Altium Limited"))
      (libsource (lib "") (part "RES_08_2"))
    )
    (comp (ref "R97")
      (value "10R")
      (footprint "R0805")
      (description "Tr? 0805 1%")
      (fields (field (name "PUBLISHER") "Altium Limited"))
      (libsource (lib "Schematic") (part "RES_08"))
    )
    (comp (ref "R99")
      (value "10K")
      (footprint "R0805")
      (description "Tr? 0805 1%")
      (fields (field (name "PUBLISHER") "Altium Limited"))
      (libsource (lib "") (part "RES_08_2"))
    )
    (comp (ref "R101")
      (value "10R")
      (footprint "R0805")
      (description "Tr? 0805 1%")
      (fields (field (name "PUBLISHER") "Altium Limited"))
      (libsource (lib "Schematic") (part "RES_08"))
    )
    (comp (ref "R103")
      (value "10K")
      (footprint "R0805")
      (description "Tr? 0805 1%")
      (fields (field (name "PUBLISHER") "Altium Limited"))
      (libsource (lib "") (part "RES_08_2"))
    )
    (comp (ref "R106")
      (value "10R")
      (footprint "R0805")
      (description "Tr? 0805 1%")
      (fields (field (name "PUBLISHER") "Altium Limited"))
      (libsource (lib "Schematic") (part "RES_08"))
    )
    (comp (ref "R108")
      (value "1K")
      (footprint "R0805")
      (description "Tr? 0805 1%")
      (fields (field (name "PUBLISHER") "Altium Limited"))
      (libsource (lib "") (part "RES_08_1"))
    )
    (comp (ref "RS1")
      (value "SW")
      (footprint "SW1-SMD")
      (description "Switch button 2 pin")
      (libsource (lib "TechMT.VN_Lib_Project v2") (part "SW2"))
    )
    (comp (ref "SW1")
      (value "SW")
      (footprint "SW2-DIP")
      (description "Switch button 4 pin")
      (libsource (lib "TechMT.VN_Lib_Project v2") (part "SW4"))
    )
    (comp (ref "SW2")
      (value "SW")
      (footprint "SW2-DIP")
      (description "Switch button 4 pin")
      (libsource (lib "TechMT.VN_Lib_Project v2") (part "SW4"))
    )
    (comp (ref "U1")
      (value "74HC595")
      (footprint "74HC595")
      (libsource (lib "TDX_Local_LIbrary") (part "74HC595"))
    )
    (comp (ref "U2")
      (value "74HC595")
      (footprint "74HC595")
      (libsource (lib "TDX_Local_LIbrary") (part "74HC595"))
    )
    (comp (ref "U3")
      (value "74HC595")
      (footprint "74HC595")
      (libsource (lib "TDX_Local_LIbrary") (part "74HC595"))
    )
    (comp (ref "U4")
      (value "74HC595")
      (footprint "74HC595")
      (libsource (lib "TDX_Local_LIbrary") (part "74HC595"))
    )
    (comp (ref "U5")
      (value "XL1509")
      (footprint "SO8_N")
      (description "XL1509-5.0 SOP8 DC-DC 2A 5V")
      (libsource (lib "Sonar 2019_Ver3.0") (part "XL1509"))
    )
    (comp (ref "Uart1")
      (value "Jump 4p")
      (footprint "Jump 4p")
      (libsource (lib "TDX_Local_LIbrary") (part "Jump 4p"))
    )
  )
  (nets
    (net (code "1") (name "+5V") (class "Default")
      (node (ref "C1") (pin "1") (pinfunction "1_1") (pintype "passive"))
      (node (ref "C11") (pin "3") (pinfunction "3_3") (pintype "passive"))
      (node (ref "C12") (pin "3") (pinfunction "3_3") (pintype "passive"))
      (node (ref "C14") (pin "1") (pinfunction "1_1") (pintype "passive"))
      (node (ref "C15") (pin "2") (pinfunction "2_2") (pintype "passive"))
      (node (ref "C3") (pin "1") (pinfunction "1_1") (pintype "passive"))
      (node (ref "C5") (pin "1") (pinfunction "1_1") (pintype "passive"))
      (node (ref "C9") (pin "1") (pinfunction "1_1") (pintype "passive"))
      (node (ref "IC1") (pin "3") (pinfunction "IN_3") (pintype "passive"))
      (node (ref "L1") (pin "2") (pinfunction "2_2") (pintype "passive"))
      (node (ref "U1") (pin "10") (pinfunction "~{RST}_10") (pintype "input"))
      (node (ref "U1") (pin "16") (pinfunction "VDD_16") (pintype "power_in"))
      (node (ref "U2") (pin "10") (pinfunction "~{RST}_10") (pintype "input"))
      (node (ref "U2") (pin "16") (pinfunction "VDD_16") (pintype "power_in"))
      (node (ref "U3") (pin "10") (pinfunction "~{RST}_10") (pintype "input"))
      (node (ref "U3") (pin "16") (pinfunction "VDD_16") (pintype "power_in"))
      (node (ref "U4") (pin "10") (pinfunction "~{RST}_10") (pintype "input"))
      (node (ref "U4") (pin "16") (pinfunction "VDD_16") (pintype "power_in"))
      (node (ref "U5") (pin "3") (pinfunction "FB_3") (pintype "passive"))
    )
    (net (code "2") (name "+12") (class "Default")
      (node (ref "D1") (pin "1") (pinfunction "A_1") (pintype "passive"))
      (node (ref "HD1") (pin "1") (pinfunction "1_1") (pintype "passive"))
    )
    (net (code "4") (name "/A0") (class "Default")
      (node (ref "ESP1") (pin "2") (pinfunction "ADC_2") (pintype "passive"))
      (node (ref "R58") (pin "1") (pinfunction "1_1") (pintype "passive"))
      (node (ref "R65") (pin "2") (pinfunction "2_2") (pintype "passive"))
    )
    (net (code "5") (name "/ADC") (class "Default")
      (node (ref "C17") (pin "1") (pinfunction "1_1") (pintype "passive"))
      (node (ref "H1") (pin "2") (pinfunction "2_2") (pintype "passive"))
      (node (ref "R58") (pin "2") (pinfunction "2_2") (pintype "passive"))
      (node (ref "R80") (pin "2") (pinfunction "2_2") (pintype "passive"))
    )
    (net (code "6") (name "/CLK") (class "Default")
      (node (ref "ESP1") (pin "17") (pinfunction "IO2_17") (pintype "bidirectional"))
      (node (ref "R68") (pin "1") (pinfunction "1_1") (pintype "passive"))
      (node (ref "U1") (pin "11") (pinfunction "SHCP_11") (pintype "input"))
      (node (ref "U2") (pin "11") (pinfunction "SHCP_11") (pintype "input"))
      (node (ref "U3") (pin "11") (pinfunction "SHCP_11") (pintype "input"))
      (node (ref "U4") (pin "11") (pinfunction "SHCP_11") (pintype "input"))
    )
    (net (code "7") (name "/D0") (class "Default")
      (node (ref "ESP1") (pin "4") (pinfunction "IO16_4") (pintype "bidirectional"))
    )
    (net (code "8") (name "/D1") (class "Default")
      (node (ref "ESP1") (pin "20") (pinfunction "IO5_20") (pintype "bidirectional"))
      (node (ref "SW2") (pin "2") (pinfunction "2_2") (pintype "passive"))
    )
    (net (code "9") (name "/D2") (class "Default")
      (node (ref "ESP1") (pin "19") (pinfunction "IO4_19") (pintype "bidirectional"))
      (node (ref "SW1") (pin "2") (pinfunction "2_2") (pintype "passive"))
    )
    (net (code "10") (name "/D3") (class "Default")
      (node (ref "ESP1") (pin "18") (pinfunction "IO0_18") (pintype "bidirectional"))
      (node (ref "Flash1") (pin "2") (pinfunction "2_2") (pintype "passive"))
      (node (ref "R62") (pin "1") (pinfunction "1_1") (pintype "passive"))
      (node (ref "U1") (pin "12") (pinfunction "STCP_12") (pintype "input"))
      (node (ref "U2") (pin "12") (pinfunction "STCP_12") (pintype "input"))
      (node (ref "U3") (pin "12") (pinfunction "STCP_12") (pintype "input"))
      (node (ref "U4") (pin "12") (pinfunction "STCP_12") (pintype "input"))
    )
    (net (code "11") (name "/D5") (class "Default")
      (node (ref "C11") (pin "2") (pinfunction "2_2") (pintype "passive"))
      (node (ref "ESP1") (pin "5") (pinfunction "IO14_5") (pintype "bidirectional"))
    )
    (net (code "12") (name "/D6") (class "Default")
      (node (ref "C12") (pin "2") (pinfunction "2_2") (pintype "passive"))
      (node (ref "ESP1") (pin "6") (pinfunction "IO12_6") (pintype "bidirectional"))
    )
    (net (code "13") (name "/D7") (class "Default")
      (node (ref "ESP1") (pin "7") (pinfunction "IO13_7") (pintype "bidirectional"))
      (node (ref "U1") (pin "14") (pinfunction "DS_14") (pintype "input"))
    )
    (net (code "14") (name "/D8") (class "Default")
      (node (ref "ESP1") (pin "16") (pinfunction "IO15_16") (pintype "bidirectional"))
      (node (ref "R69") (pin "2") (pinfunction "2_2") (pintype "passive"))
    )
    (net (code "15") (name "/EN") (class "Default")
      (node (ref "ESP1") (pin "3") (pinfunction "EN_3") (pintype "input"))
      (node (ref "R57") (pin "1") (pinfunction "1_1") (pintype "passive"))
    )
    (net (code "16") (name "/O0_HC") (class "Default")
      (node (ref "R21") (pin "1") (pinfunction "1_1") (pintype "passive"))
      (node (ref "R3") (pin "2") (pinfunction "2_2") (pintype "passive"))
      (node (ref "U1") (pin "15") (pinfunction "QA_15") (pintype "tri_state"))
    )
    (net (code "17") (name "/O1_HC") (class "Default")
      (node (ref "R20") (pin "1") (pinfunction "1_1") (pintype "passive"))
      (node (ref "R8") (pin "2") (pinfunction "2_2") (pintype "passive"))
      (node (ref "U1") (pin "1") (pinfunction "QB_1") (pintype "tri_state"))
    )
    (net (code "18") (name "/O2_HC") (class "Default")
      (node (ref "R12") (pin "2") (pinfunction "2_2") (pintype "passive"))
      (node (ref "R19") (pin "1") (pinfunction "1_1") (pintype "passive"))
      (node (ref "U1") (pin "2") (pinfunction "QC_2") (pintype "tri_state"))
    )
    (net (code "19") (name "/O3_HC") (class "Default")
      (node (ref "R18") (pin "1") (pinfunction "1_1") (pintype "passive"))
      (node (ref "R32") (pin "2") (pinfunction "2_2") (pintype "passive"))
      (node (ref "U1") (pin "3") (pinfunction "QD_3") (pintype "tri_state"))
    )
    (net (code "20") (name "/O4_HC") (class "Default")
      (node (ref "R17") (pin "1") (pinfunction "1_1") (pintype "passive"))
      (node (ref "R36") (pin "2") (pinfunction "2_2") (pintype "passive"))
      (node (ref "U1") (pin "4") (pinfunction "QE_4") (pintype "tri_state"))
    )
    (net (code "21") (name "/O5_HC") (class "Default")
      (node (ref "R16") (pin "1") (pinfunction "1_1") (pintype "passive"))
      (node (ref "R40") (pin "2") (pinfunction "2_2") (pintype "passive"))
      (node (ref "U1") (pin "5") (pinfunction "QF_5") (pintype "tri_state"))
    )
    (net (code "22") (name "/O6_HC") (class "Default")
      (node (ref "R15") (pin "1") (pinfunction "1_1") (pintype "passive"))
      (node (ref "R45") (pin "2") (pinfunction "2_2") (pintype "passive"))
      (node (ref "U1") (pin "6") (pinfunction "QG_6") (pintype "tri_state"))
    )
    (net (code "23") (name "/O7_HC") (class "Default")
      (node (ref "R14") (pin "1") (pinfunction "1_1") (pintype "passive"))
      (node (ref "R49") (pin "2") (pinfunction "2_2") (pintype "passive"))
      (node (ref "U1") (pin "7") (pinfunction "QH_7") (pintype "tri_state"))
    )
    (net (code "24") (name "/O8_HC") (class "Default")
      (node (ref "R54") (pin "2") (pinfunction "2_2") (pintype "passive"))
      (node (ref "R78") (pin "1") (pinfunction "1_1") (pintype "passive"))
      (node (ref "U2") (pin "15") (pinfunction "QA_15") (pintype "tri_state"))
    )
    (net (code "25") (name "/O9_HC") (class "Default")
      (node (ref "R60") (pin "2") (pinfunction "2_2") (pintype "passive"))
      (node (ref "R77") (pin "1") (pinfunction "1_1") (pintype "passive"))
      (node (ref "U2") (pin "1") (pinfunction "QB_1") (pintype "tri_state"))
    )
    (net (code "26") (name "/O10_HC") (class "Default")
      (node (ref "R67") (pin "2") (pinfunction "2_2") (pintype "passive"))
      (node (ref "R76") (pin "1") (pinfunction "1_1") (pintype "passive"))
      (node (ref "U2") (pin "2") (pinfunction "QC_2") (pintype "tri_state"))
    )
    (net (code "27") (name "/O11_HC") (class "Default")
      (node (ref "R75") (pin "1") (pinfunction "1_1") (pintype "passive"))
      (node (ref "R89") (pin "2") (pinfunction "2_2") (pintype "passive"))
      (node (ref "U2") (pin "3") (pinfunction "QD_3") (pintype "tri_state"))
    )
    (net (code "28") (name "/O12_HC") (class "Default")
      (node (ref "R74") (pin "1") (pinfunction "1_1") (pintype "passive"))
      (node (ref "R93") (pin "2") (pinfunction "2_2") (pintype "passive"))
      (node (ref "U2") (pin "4") (pinfunction "QE_4") (pintype "tri_state"))
    )
    (net (code "29") (name "/O13_HC") (class "Default")
      (node (ref "R73") (pin "1") (pinfunction "1_1") (pintype "passive"))
      (node (ref "R97") (pin "2") (pinfunction "2_2") (pintype "passive"))
      (node (ref "U2") (pin "5") (pinfunction "QF_5") (pintype "tri_state"))
    )
    (net (code "30") (name "/O14_HC") (class "Default")
      (node (ref "R101") (pin "2") (pinfunction "2_2") (pintype "passive"))
      (node (ref "R72") (pin "1") (pinfunction "1_1") (pintype "passive"))
      (node (ref "U2") (pin "6") (pinfunction "QG_6") (pintype "tri_state"))
    )
    (net (code "31") (name "/O15_HC") (class "Default")
      (node (ref "R106") (pin "2") (pinfunction "2_2") (pintype "passive"))
      (node (ref "R71") (pin "1") (pinfunction "1_1") (pintype "passive"))
      (node (ref "U2") (pin "7") (pinfunction "QH_7") (pintype "tri_state"))
    )
    (net (code "32") (name "/O16_HC") (class "Default")
      (node (ref "R30") (pin "1") (pinfunction "1_1") (pintype "passive"))
      (node (ref "R4") (pin "2") (pinfunction "2_2") (pintype "passive"))
      (node (ref "U3") (pin "15") (pinfunction "QA_15") (pintype "tri_state"))
    )
    (net (code "33") (name "/O17_HC") (class "Default")
      (node (ref "R29") (pin "1") (pinfunction "1_1") (pintype "passive"))
      (node (ref "R9") (pin "2") (pinfunction "2_2") (pintype "passive"))
      (node (ref "U3") (pin "1") (pinfunction "QB_1") (pintype "tri_state"))
    )
    (net (code "34") (name "/O18_HC") (class "Default")
      (node (ref "R13") (pin "2") (pinfunction "2_2") (pintype "passive"))
      (node (ref "R28") (pin "1") (pinfunction "1_1") (pintype "passive"))
      (node (ref "U3") (pin "2") (pinfunction "QC_2") (pintype "tri_state"))
    )
    (net (code "35") (name "/O19_HC") (class "Default")
      (node (ref "R27") (pin "1") (pinfunction "1_1") (pintype "passive"))
      (node (ref "R33") (pin "2") (pinfunction "2_2") (pintype "passive"))
      (node (ref "U3") (pin "3") (pinfunction "QD_3") (pintype "tri_state"))
    )
    (net (code "36") (name "/O20_HC") (class "Default")
      (node (ref "R26") (pin "1") (pinfunction "1_1") (pintype "passive"))
      (node (ref "R37") (pin "2") (pinfunction "2_2") (pintype "passive"))
      (node (ref "U3") (pin "4") (pinfunction "QE_4") (pintype "tri_state"))
    )
    (net (code "37") (name "/O21_HC") (class "Default")
      (node (ref "R25") (pin "1") (pinfunction "1_1") (pintype "passive"))
      (node (ref "R41") (pin "2") (pinfunction "2_2") (pintype "passive"))
      (node (ref "U3") (pin "5") (pinfunction "QF_5") (pintype "tri_state"))
    )
    (net (code "38") (name "/O22_HC") (class "Default")
      (node (ref "R24") (pin "1") (pinfunction "1_1") (pintype "passive"))
      (node (ref "R46") (pin "2") (pinfunction "2_2") (pintype "passive"))
      (node (ref "U3") (pin "6") (pinfunction "QG_6") (pintype "tri_state"))
    )
    (net (code "39") (name "/O23_HC") (class "Default")
      (node (ref "R23") (pin "1") (pinfunction "1_1") (pintype "passive"))
      (node (ref "R50") (pin "2") (pinfunction "2_2") (pintype "passive"))
      (node (ref "U3") (pin "7") (pinfunction "QH_7") (pintype "tri_state"))
    )
    (net (code "40") (name "/O24_HC") (class "Default")
      (node (ref "R55") (pin "2") (pinfunction "2_2") (pintype "passive"))
      (node (ref "R87") (pin "1") (pinfunction "1_1") (pintype "passive"))
      (node (ref "U4") (pin "15") (pinfunction "QA_15") (pintype "tri_state"))
    )
    (net (code "41") (name "/O25_HC") (class "Default")
      (node (ref "R61") (pin "2") (pinfunction "2_2") (pintype "passive"))
      (node (ref "R86") (pin "1") (pinfunction "1_1") (pintype "passive"))
      (node (ref "U4") (pin "1") (pinfunction "QB_1") (pintype "tri_state"))
    )
    (net (code "42") (name "/O26_HC") (class "Default")
      (node (ref "R70") (pin "2") (pinfunction "2_2") (pintype "passive"))
      (node (ref "R85") (pin "1") (pinfunction "1_1") (pintype "passive"))
      (node (ref "U4") (pin "2") (pinfunction "QC_2") (pintype "tri_state"))
    )
    (net (code "43") (name "/O27_HC") (class "Default")
      (node (ref "U4") (pin "3") (pinfunction "QD_3") (pintype "tri_state"))
    )
    (net (code "44") (name "/O28_HC") (class "Default")
      (node (ref "U4") (pin "4") (pinfunction "QE_4") (pintype "tri_state"))
    )
    (net (code "45") (name "/O29_HC") (class "Default")
      (node (ref "U4") (pin "5") (pinfunction "QF_5") (pintype "tri_state"))
    )
    (net (code "46") (name "/O30_HC") (class "Default")
      (node (ref "U4") (pin "6") (pinfunction "QG_6") (pintype "tri_state"))
    )
    (net (code "47") (name "/O31_HC") (class "Default")
      (node (ref "U4") (pin "7") (pinfunction "QH_7") (pintype "tri_state"))
    )
    (net (code "48") (name "/RS") (class "Default")
      (node (ref "ESP1") (pin "1") (pinfunction "RESET_1") (pintype "input"))
      (node (ref "R52") (pin "1") (pinfunction "1_1") (pintype "passive"))
      (node (ref "RS1") (pin "2") (pinfunction "2_2") (pintype "passive"))
    )
    (net (code "49") (name "/RX") (class "Default")
      (node (ref "ESP1") (pin "21") (pinfunction "RXD_21") (pintype "input"))
      (node (ref "Uart1") (pin "4") (pinfunction "4_4") (pintype "passive"))
    )
    (net (code "50") (name "/TX") (class "Default")
      (node (ref "ESP1") (pin "22") (pinfunction "TXD_22") (pintype "output"))
      (node (ref "Uart1") (pin "3") (pinfunction "3_3") (pintype "passive"))
    )
    (net (code "51") (name "3.3V") (class "Default")
      (node (ref "C16") (pin "2") (pinfunction "2_2") (pintype "passive"))
      (node (ref "C7") (pin "2") (pinfunction "2_2") (pintype "passive"))
      (node (ref "C8") (pin "2") (pinfunction "2_2") (pintype "passive"))
      (node (ref "ESP1") (pin "8") (pinfunction "VCC_8") (pintype "power_in"))
      (node (ref "IC1") (pin "2") (pinfunction "OUT_2") (pintype "passive"))
      (node (ref "IC1") (pin "4") (pinfunction "Tab_4") (pintype "passive"))
      (node (ref "R52") (pin "2") (pinfunction "2_2") (pintype "passive"))
      (node (ref "R57") (pin "2") (pinfunction "2_2") (pintype "passive"))
      (node (ref "R62") (pin "2") (pinfunction "2_2") (pintype "passive"))
      (node (ref "R68") (pin "2") (pinfunction "2_2") (pintype "passive"))
      (node (ref "R80") (pin "1") (pinfunction "1_1") (pintype "passive"))
      (node (ref "Uart1") (pin "1") (pinfunction "1_1") (pintype "passive"))
      (node (ref "led33") (pin "1") (pinfunction "1_1") (pintype "passive"))
    )
    (net (code "52") (name "GND") (class "Default")
      (node (ref "C1") (pin "2") (pinfunction "2_2") (pintype "passive"))
      (node (ref "C11") (pin "1") (pinfunction "1_1") (pintype "passive"))
      (node (ref "C12") (pin "1") (pinfunction "1_1") (pintype "passive"))
      (node (ref "C13") (pin "1") (pinfunction "1_1") (pintype "passive"))
      (node (ref "C14") (pin "2") (pinfunction "2_2") (pintype "passive"))
      (node (ref "C15") (pin "1") (pinfunction "1_1") (pintype "passive"))
      (node (ref "C16") (pin "1") (pinfunction "1_1") (pintype "passive"))
      (node (ref "C17") (pin "2") (pinfunction "2_2") (pintype "passive"))
      (node (ref "C3") (pin "2") (pinfunction "2_2") (pintype "passive"))
      (node (ref "C5") (pin "2") (pinfunction "2_2") (pintype "passive"))
      (node (ref "C7") (pin "1") (pinfunction "1_1") (pintype "passive"))
      (node (ref "C8") (pin "1") (pinfunction "1_1") (pintype "passive"))
      (node (ref "C9") (pin "2") (pinfunction "2_2") (pintype "passive"))
      (node (ref "D2") (pin "1") (pinfunction "A_1") (pintype "passive"))
      (node (ref "ESP1") (pin "15") (pinfunction "GND_15") (pintype "power_in"))
      (node (ref "Flash1") (pin "1") (pinfunction "1_1") (pintype "passive"))
      (node (ref "H1") (pin "1") (pinfunction "1_1") (pintype "passive"))
      (node (ref "HD1") (pin "2") (pinfunction "2_2") (pintype "passive"))
      (node (ref "IC1") (pin "1") (pinfunction "ADJ/G_1") (pintype "passive"))
      (node (ref "Q1") (pin "3") (pinfunction "S_3") (pintype "passive"))
      (node (ref "Q10") (pin "3") (pinfunction "S_3") (pintype "passive"))
      (node (ref "Q11") (pin "3") (pinfunction "S_3") (pintype "passive"))
      (node (ref "Q12") (pin "3") (pinfunction "S_3") (pintype "passive"))
      (node (ref "Q13") (pin "3") (pinfunction "S_3") (pintype "passive"))
      (node (ref "Q14") (pin "3") (pinfunction "S_3") (pintype "passive"))
      (node (ref "Q15") (pin "3") (pinfunction "S_3") (pintype "passive"))
      (node (ref "Q16") (pin "3") (pinfunction "S_3") (pintype "passive"))
      (node (ref "Q17") (pin "3") (pinfunction "S_3") (pintype "passive"))
      (node (ref "Q18") (pin "3") (pinfunction "S_3") (pintype "passive"))
      (node (ref "Q19") (pin "3") (pinfunction "S_3") (pintype "passive"))
      (node (ref "Q2") (pin "3") (pinfunction "S_3") (pintype "passive"))
      (node (ref "Q20") (pin "3") (pinfunction "S_3") (pintype "passive"))
      (node (ref "Q21") (pin "3") (pinfunction "S_3") (pintype "passive"))
      (node (ref "Q22") (pin "3") (pinfunction "S_3") (pintype "passive"))
      (node (ref "Q23") (pin "3") (pinfunction "S_3") (pintype "passive"))
      (node (ref "Q25") (pin "3") (pinfunction "S_3") (pintype "passive"))
      (node (ref "Q27") (pin "3") (pinfunction "S_3") (pintype "passive"))
      (node (ref "Q29") (pin "3") (pinfunction "S_3") (pintype "passive"))
      (node (ref "Q3") (pin "3") (pinfunction "S_3") (pintype "passive"))
      (node (ref "Q31") (pin "3") (pinfunction "S_3") (pintype "passive"))
      (node (ref "Q4") (pin "3") (pinfunction "S_3") (pintype "passive"))
      (node (ref "Q5") (pin "3") (pinfunction "S_3") (pintype "passive"))
      (node (ref "Q6") (pin "3") (pinfunction "S_3") (pintype "passive"))
      (node (ref "Q7") (pin "3") (pinfunction "S_3") (pintype "passive"))
      (node (ref "Q8") (pin "3") (pinfunction "S_3") (pintype "passive"))
      (node (ref "Q9") (pin "3") (pinfunction "S_3") (pintype "passive"))
      (node (ref "R1") (pin "2") (pinfunction "2_2") (pintype "passive"))
      (node (ref "R10") (pin "2") (pinfunction "2_2") (pintype "passive"))
      (node (ref "R103") (pin "2") (pinfunction "2_2") (pintype "passive"))
      (node (ref "R108") (pin "2") (pinfunction "2_2") (pintype "passive"))
      (node (ref "R11") (pin "2") (pinfunction "2_2") (pintype "passive"))
      (node (ref "R2") (pin "2") (pinfunction "2_2") (pintype "passive"))
      (node (ref "R22") (pin "2") (pinfunction "2_2") (pintype "passive"))
      (node (ref "R31") (pin "2") (pinfunction "2_2") (pintype "passive"))
      (node (ref "R34") (pin "2") (pinfunction "2_2") (pintype "passive"))
      (node (ref "R35") (pin "2") (pinfunction "2_2") (pintype "passive"))
      (node (ref "R38") (pin "2") (pinfunction "2_2") (pintype "passive"))
      (node (ref "R39") (pin "2") (pinfunction "2_2") (pintype "passive"))
      (node (ref "R43") (pin "2") (pinfunction "2_2") (pintype "passive"))
      (node (ref "R44") (pin "2") (pinfunction "2_2") (pintype "passive"))
      (node (ref "R47") (pin "2") (pinfunction "2_2") (pintype "passive"))
      (node (ref "R48") (pin "2") (pinfunction "2_2") (pintype "passive"))
      (node (ref "R51") (pin "2") (pinfunction "2_2") (pintype "passive"))
      (node (ref "R53") (pin "2") (pinfunction "2_2") (pintype "passive"))
      (node (ref "R56") (pin "2") (pinfunction "2_2") (pintype "passive"))
      (node (ref "R59") (pin "2") (pinfunction "2_2") (pintype "passive"))
      (node (ref "R6") (pin "2") (pinfunction "2_2") (pintype "passive"))
      (node (ref "R64") (pin "2") (pinfunction "2_2") (pintype "passive"))
      (node (ref "R65") (pin "1") (pinfunction "1_1") (pintype "passive"))
      (node (ref "R66") (pin "2") (pinfunction "2_2") (pintype "passive"))
      (node (ref "R69") (pin "1") (pinfunction "1_1") (pintype "passive"))
      (node (ref "R7") (pin "2") (pinfunction "2_2") (pintype "passive"))
      (node (ref "R79") (pin "2") (pinfunction "2_2") (pintype "passive"))
      (node (ref "R91") (pin "2") (pinfunction "2_2") (pintype "passive"))
      (node (ref "R95") (pin "2") (pinfunction "2_2") (pintype "passive"))
      (node (ref "R99") (pin "2") (pinfunction "2_2") (pintype "passive"))
      (node (ref "RS1") (pin "1") (pinfunction "1_1") (pintype "passive"))
      (node (ref "SW1") (pin "1") (pintype "passive"))
      (node (ref "SW2") (pin "1") (pintype "passive"))
      (node (ref "U1") (pin "13") (pinfunction "~{OE}_13") (pintype "input"))
      (node (ref "U1") (pin "8") (pinfunction "GND_8") (pintype "power_in"))
      (node (ref "U2") (pin "13") (pinfunction "~{OE}_13") (pintype "input"))
      (node (ref "U2") (pin "8") (pinfunction "GND_8") (pintype "power_in"))
      (node (ref "U3") (pin "13") (pinfunction "~{OE}_13") (pintype "input"))
      (node (ref "U3") (pin "8") (pinfunction "GND_8") (pintype "power_in"))
      (node (ref "U4") (pin "13") (pinfunction "~{OE}_13") (pintype "input"))
      (node (ref "U4") (pin "8") (pinfunction "GND_8") (pintype "power_in"))
      (node (ref "U5") (pin "4") (pinfunction "On/Off_4") (pintype "passive"))
      (node (ref "U5") (pin "5") (pinfunction "GND_5") (pintype "passive"))
      (node (ref "U5") (pin "6") (pinfunction "GND_6") (pintype "passive"))
      (node (ref "U5") (pin "7") (pinfunction "GND_7") (pintype "passive"))
      (node (ref "U5") (pin "8") (pinfunction "GND_8") (pintype "passive"))
      (node (ref "Uart1") (pin "2") (pinfunction "2_2") (pintype "passive"))
      (node (ref "led1") (pin "2") (pinfunction "2_2") (pintype "passive"))
      (node (ref "led10") (pin "2") (pinfunction "2_2") (pintype "passive"))
      (node (ref "led11") (pin "2") (pinfunction "2_2") (pintype "passive"))
      (node (ref "led12") (pin "2") (pinfunction "2_2") (pintype "passive"))
      (node (ref "led13") (pin "2") (pinfunction "2_2") (pintype "passive"))
      (node (ref "led14") (pin "2") (pinfunction "2_2") (pintype "passive"))
      (node (ref "led15") (pin "2") (pinfunction "2_2") (pintype "passive"))
      (node (ref "led16") (pin "2") (pinfunction "2_2") (pintype "passive"))
      (node (ref "led17") (pin "2") (pinfunction "2_2") (pintype "passive"))
      (node (ref "led18") (pin "2") (pinfunction "2_2") (pintype "passive"))
      (node (ref "led19") (pin "2") (pinfunction "2_2") (pintype "passive"))
      (node (ref "led2") (pin "2") (pinfunction "2_2") (pintype "passive"))
      (node (ref "led20") (pin "2") (pinfunction "2_2") (pintype "passive"))
      (node (ref "led21") (pin "2") (pinfunction "2_2") (pintype "passive"))
      (node (ref "led22") (pin "2") (pinfunction "2_2") (pintype "passive"))
      (node (ref "led23") (pin "2") (pinfunction "2_2") (pintype "passive"))
      (node (ref "led24") (pin "2") (pinfunction "2_2") (pintype "passive"))
      (node (ref "led3") (pin "2") (pinfunction "2_2") (pintype "passive"))
      (node (ref "led30") (pin "2") (pinfunction "2_2") (pintype "passive"))
      (node (ref "led31") (pin "2") (pinfunction "2_2") (pintype "passive"))
      (node (ref "led32") (pin "2") (pinfunction "2_2") (pintype "passive"))
      (node (ref "led4") (pin "2") (pinfunction "2_2") (pintype "passive"))
      (node (ref "led5") (pin "2") (pinfunction "2_2") (pintype "passive"))
      (node (ref "led6") (pin "2") (pinfunction "2_2") (pintype "passive"))
      (node (ref "led7") (pin "2") (pinfunction "2_2") (pintype "passive"))
      (node (ref "led8") (pin "2") (pinfunction "2_2") (pintype "passive"))
      (node (ref "led9") (pin "2") (pinfunction "2_2") (pintype "passive"))
    )
    (net (code "53") (name "Net-(D2-K)") (class "Default")
      (node (ref "D2") (pin "2") (pinfunction "K_2") (pintype "passive"))
      (node (ref "L1") (pin "1") (pinfunction "1_1") (pintype "passive"))
      (node (ref "U5") (pin "2") (pinfunction "Vout_2") (pintype "passive"))
    )
    (net (code "54") (name "Net-(Q1-D)") (class "Default")
      (node (ref "J1") (pin "1") (pinfunction "1_1") (pintype "passive"))
      (node (ref "Q1") (pin "4") (pinfunction "D_4") (pintype "passive"))
    )
    (net (code "55") (name "Net-(Q1-G)") (class "Default")
      (node (ref "Q1") (pin "1") (pinfunction "G_1") (pintype "passive"))
      (node (ref "R1") (pin "1") (pinfunction "1_1") (pintype "passive"))
      (node (ref "R3") (pin "1") (pinfunction "1_1") (pintype "passive"))
    )
    (net (code "56") (name "Net-(Q2-D)") (class "Default")
      (node (ref "J2") (pin "1") (pinfunction "1_1") (pintype "passive"))
      (node (ref "Q2") (pin "4") (pinfunction "D_4") (pintype "passive"))
    )
    (net (code "57") (name "Net-(Q2-G)") (class "Default")
      (node (ref "Q2") (pin "1") (pinfunction "G_1") (pintype "passive"))
      (node (ref "R2") (pin "1") (pinfunction "1_1") (pintype "passive"))
      (node (ref "R4") (pin "1") (pinfunction "1_1") (pintype "passive"))
    )
    (net (code "58") (name "Net-(Q3-D)") (class "Default")
      (node (ref "J1") (pin "2") (pinfunction "2_2") (pintype "passive"))
      (node (ref "Q3") (pin "4") (pinfunction "D_4") (pintype "passive"))
    )
    (net (code "59") (name "Net-(Q3-G)") (class "Default")
      (node (ref "Q3") (pin "1") (pinfunction "G_1") (pintype "passive"))
      (node (ref "R6") (pin "1") (pinfunction "1_1") (pintype "passive"))
      (node (ref "R8") (pin "1") (pinfunction "1_1") (pintype "passive"))
    )
    (net (code "60") (name "Net-(Q4-D)") (class "Default")
      (node (ref "J2") (pin "2") (pinfunction "2_2") (pintype "passive"))
      (node (ref "Q4") (pin "4") (pinfunction "D_4") (pintype "passive"))
    )
    (net (code "61") (name "Net-(Q4-G)") (class "Default")
      (node (ref "Q4") (pin "1") (pinfunction "G_1") (pintype "passive"))
      (node (ref "R7") (pin "1") (pinfunction "1_1") (pintype "passive"))
      (node (ref "R9") (pin "1") (pinfunction "1_1") (pintype "passive"))
    )
    (net (code "62") (name "Net-(Q5-D)") (class "Default")
      (node (ref "J3") (pin "1") (pinfunction "1_1") (pintype "passive"))
      (node (ref "Q5") (pin "4") (pinfunction "D_4") (pintype "passive"))
    )
    (net (code "63") (name "Net-(Q5-G)") (class "Default")
      (node (ref "Q5") (pin "1") (pinfunction "G_1") (pintype "passive"))
      (node (ref "R10") (pin "1") (pinfunction "1_1") (pintype "passive"))
      (node (ref "R12") (pin "1") (pinfunction "1_1") (pintype "passive"))
    )
    (net (code "64") (name "Net-(Q6-D)") (class "Default")
      (node (ref "J4") (pin "1") (pinfunction "1_1") (pintype "passive"))
      (node (ref "Q6") (pin "4") (pinfunction "D_4") (pintype "passive"))
    )
    (net (code "65") (name "Net-(Q6-G)") (class "Default")
      (node (ref "Q6") (pin "1") (pinfunction "G_1") (pintype "passive"))
      (node (ref "R11") (pin "1") (pinfunction "1_1") (pintype "passive"))
      (node (ref "R13") (pin "1") (pinfunction "1_1") (pintype "passive"))
    )
    (net (code "66") (name "Net-(Q7-D)") (class "Default")
      (node (ref "J3") (pin "2") (pinfunction "2_2") (pintype "passive"))
      (node (ref "Q7") (pin "4") (pinfunction "D_4") (pintype "passive"))
    )
    (net (code "67") (name "Net-(Q7-G)") (class "Default")
      (node (ref "Q7") (pin "1") (pinfunction "G_1") (pintype "passive"))
      (node (ref "R22") (pin "1") (pinfunction "1_1") (pintype "passive"))
      (node (ref "R32") (pin "1") (pinfunction "1_1") (pintype "passive"))
    )
    (net (code "68") (name "Net-(Q8-D)") (class "Default")
      (node (ref "J4") (pin "2") (pinfunction "2_2") (pintype "passive"))
      (node (ref "Q8") (pin "4") (pinfunction "D_4") (pintype "passive"))
    )
    (net (code "69") (name "Net-(Q8-G)") (class "Default")
      (node (ref "Q8") (pin "1") (pinfunction "G_1") (pintype "passive"))
      (node (ref "R31") (pin "1") (pinfunction "1_1") (pintype "passive"))
      (node (ref "R33") (pin "1") (pinfunction "1_1") (pintype "passive"))
    )
    (net (code "70") (name "Net-(Q9-D)") (class "Default")
      (node (ref "J5") (pin "1") (pinfunction "1_1") (pintype "passive"))
      (node (ref "Q9") (pin "4") (pinfunction "D_4") (pintype "passive"))
    )
    (net (code "71") (name "Net-(Q9-G)") (class "Default")
      (node (ref "Q9") (pin "1") (pinfunction "G_1") (pintype "passive"))
      (node (ref "R34") (pin "1") (pinfunction "1_1") (pintype "passive"))
      (node (ref "R36") (pin "1") (pinfunction "1_1") (pintype "passive"))
    )
    (net (code "72") (name "Net-(Q10-D)") (class "Default")
      (node (ref "J6") (pin "1") (pinfunction "1_1") (pintype "passive"))
      (node (ref "Q10") (pin "4") (pinfunction "D_4") (pintype "passive"))
    )
    (net (code "73") (name "Net-(Q10-G)") (class "Default")
      (node (ref "Q10") (pin "1") (pinfunction "G_1") (pintype "passive"))
      (node (ref "R35") (pin "1") (pinfunction "1_1") (pintype "passive"))
      (node (ref "R37") (pin "1") (pinfunction "1_1") (pintype "passive"))
    )
    (net (code "74") (name "Net-(Q11-D)") (class "Default")
      (node (ref "J5") (pin "2") (pinfunction "2_2") (pintype "passive"))
      (node (ref "Q11") (pin "4") (pinfunction "D_4") (pintype "passive"))
    )
    (net (code "75") (name "Net-(Q11-G)") (class "Default")
      (node (ref "Q11") (pin "1") (pinfunction "G_1") (pintype "passive"))
      (node (ref "R38") (pin "1") (pinfunction "1_1") (pintype "passive"))
      (node (ref "R40") (pin "1") (pinfunction "1_1") (pintype "passive"))
    )
    (net (code "76") (name "Net-(Q12-D)") (class "Default")
      (node (ref "J6") (pin "2") (pinfunction "2_2") (pintype "passive"))
      (node (ref "Q12") (pin "4") (pinfunction "D_4") (pintype "passive"))
    )
    (net (code "77") (name "Net-(Q12-G)") (class "Default")
      (node (ref "Q12") (pin "1") (pinfunction "G_1") (pintype "passive"))
      (node (ref "R39") (pin "1") (pinfunction "1_1") (pintype "passive"))
      (node (ref "R41") (pin "1") (pinfunction "1_1") (pintype "passive"))
    )
    (net (code "78") (name "Net-(Q13-D)") (class "Default")
      (node (ref "J7") (pin "1") (pinfunction "1_1") (pintype "passive"))
      (node (ref "Q13") (pin "4") (pinfunction "D_4") (pintype "passive"))
    )
    (net (code "79") (name "Net-(Q13-G)") (class "Default")
      (node (ref "Q13") (pin "1") (pinfunction "G_1") (pintype "passive"))
      (node (ref "R43") (pin "1") (pinfunction "1_1") (pintype "passive"))
      (node (ref "R45") (pin "1") (pinfunction "1_1") (pintype "passive"))
    )
    (net (code "80") (name "Net-(Q14-D)") (class "Default")
      (node (ref "J8") (pin "1") (pinfunction "1_1") (pintype "passive"))
      (node (ref "Q14") (pin "4") (pinfunction "D_4") (pintype "passive"))
    )
    (net (code "81") (name "Net-(Q14-G)") (class "Default")
      (node (ref "Q14") (pin "1") (pinfunction "G_1") (pintype "passive"))
      (node (ref "R44") (pin "1") (pinfunction "1_1") (pintype "passive"))
      (node (ref "R46") (pin "1") (pinfunction "1_1") (pintype "passive"))
    )
    (net (code "82") (name "Net-(Q15-D)") (class "Default")
      (node (ref "J7") (pin "2") (pinfunction "2_2") (pintype "passive"))
      (node (ref "Q15") (pin "4") (pinfunction "D_4") (pintype "passive"))
    )
    (net (code "83") (name "Net-(Q15-G)") (class "Default")
      (node (ref "Q15") (pin "1") (pinfunction "G_1") (pintype "passive"))
      (node (ref "R47") (pin "1") (pinfunction "1_1") (pintype "passive"))
      (node (ref "R49") (pin "1") (pinfunction "1_1") (pintype "passive"))
    )
    (net (code "84") (name "Net-(Q16-D)") (class "Default")
      (node (ref "J8") (pin "2") (pinfunction "2_2") (pintype "passive"))
      (node (ref "Q16") (pin "4") (pinfunction "D_4") (pintype "passive"))
    )
    (net (code "85") (name "Net-(Q16-G)") (class "Default")
      (node (ref "Q16") (pin "1") (pinfunction "G_1") (pintype "passive"))
      (node (ref "R48") (pin "1") (pinfunction "1_1") (pintype "passive"))
      (node (ref "R50") (pin "1") (pinfunction "1_1") (pintype "passive"))
    )
    (net (code "86") (name "Net-(Q17-D)") (class "Default")
      (node (ref "J9") (pin "1") (pinfunction "1_1") (pintype "passive"))
      (node (ref "Q17") (pin "4") (pinfunction "D_4") (pintype "passive"))
    )
    (net (code "87") (name "Net-(Q17-G)") (class "Default")
      (node (ref "Q17") (pin "1") (pinfunction "G_1") (pintype "passive"))
      (node (ref "R51") (pin "1") (pinfunction "1_1") (pintype "passive"))
      (node (ref "R54") (pin "1") (pinfunction "1_1") (pintype "passive"))
    )
    (net (code "88") (name "Net-(Q18-D)") (class "Default")
      (node (ref "J10") (pin "1") (pinfunction "1_1") (pintype "passive"))
      (node (ref "Q18") (pin "4") (pinfunction "D_4") (pintype "passive"))
    )
    (net (code "89") (name "Net-(Q18-G)") (class "Default")
      (node (ref "Q18") (pin "1") (pinfunction "G_1") (pintype "passive"))
      (node (ref "R53") (pin "1") (pinfunction "1_1") (pintype "passive"))
      (node (ref "R55") (pin "1") (pinfunction "1_1") (pintype "passive"))
    )
    (net (code "90") (name "Net-(Q19-D)") (class "Default")
      (node (ref "J9") (pin "2") (pinfunction "2_2") (pintype "passive"))
      (node (ref "Q19") (pin "4") (pinfunction "D_4") (pintype "passive"))
    )
    (net (code "91") (name "Net-(Q19-G)") (class "Default")
      (node (ref "Q19") (pin "1") (pinfunction "G_1") (pintype "passive"))
      (node (ref "R56") (pin "1") (pinfunction "1_1") (pintype "passive"))
      (node (ref "R60") (pin "1") (pinfunction "1_1") (pintype "passive"))
    )
    (net (code "92") (name "Net-(Q20-D)") (class "Default")
      (node (ref "J10") (pin "2") (pinfunction "2_2") (pintype "passive"))
      (node (ref "Q20") (pin "4") (pinfunction "D_4") (pintype "passive"))
    )
    (net (code "93") (name "Net-(Q20-G)") (class "Default")
      (node (ref "Q20") (pin "1") (pinfunction "G_1") (pintype "passive"))
      (node (ref "R59") (pin "1") (pinfunction "1_1") (pintype "passive"))
      (node (ref "R61") (pin "1") (pinfunction "1_1") (pintype "passive"))
    )
    (net (code "94") (name "Net-(Q21-D)") (class "Default")
      (node (ref "J11") (pin "1") (pinfunction "1_1") (pintype "passive"))
      (node (ref "Q21") (pin "4") (pinfunction "D_4") (pintype "passive"))
    )
    (net (code "95") (name "Net-(Q21-G)") (class "Default")
      (node (ref "Q21") (pin "1") (pinfunction "G_1") (pintype "passive"))
      (node (ref "R64") (pin "1") (pinfunction "1_1") (pintype "passive"))
      (node (ref "R67") (pin "1") (pinfunction "1_1") (pintype "passive"))
    )
    (net (code "96") (name "Net-(Q22-D)") (class "Default")
      (node (ref "J12") (pin "1") (pinfunction "1_1") (pintype "passive"))
      (node (ref "Q22") (pin "4") (pinfunction "D_4") (pintype "passive"))
    )
    (net (code "97") (name "Net-(Q22-G)") (class "Default")
      (node (ref "Q22") (pin "1") (pinfunction "G_1") (pintype "passive"))
      (node (ref "R66") (pin "1") (pinfunction "1_1") (pintype "passive"))
      (node (ref "R70") (pin "1") (pinfunction "1_1") (pintype "passive"))
    )
    (net (code "98") (name "Net-(Q23-D)") (class "Default")
      (node (ref "J11") (pin "2") (pinfunction "2_2") (pintype "passive"))
      (node (ref "Q23") (pin "4") (pinfunction "D_4") (pintype "passive"))
    )
    (net (code "99") (name "Net-(Q23-G)") (class "Default")
      (node (ref "Q23") (pin "1") (pinfunction "G_1") (pintype "passive"))
      (node (ref "R79") (pin "1") (pinfunction "1_1") (pintype "passive"))
      (node (ref "R89") (pin "1") (pinfunction "1_1") (pintype "passive"))
    )
    (net (code "100") (name "Net-(Q25-D)") (class "Default")
      (node (ref "J13") (pin "1") (pinfunction "1_1") (pintype "passive"))
      (node (ref "Q25") (pin "4") (pinfunction "D_4") (pintype "passive"))
    )
    (net (code "101") (name "Net-(Q25-G)") (class "Default")
      (node (ref "Q25") (pin "1") (pinfunction "G_1") (pintype "passive"))
      (node (ref "R91") (pin "1") (pinfunction "1_1") (pintype "passive"))
      (node (ref "R93") (pin "1") (pinfunction "1_1") (pintype "passive"))
    )
    (net (code "102") (name "Net-(Q27-D)") (class "Default")
      (node (ref "J13") (pin "2") (pinfunction "2_2") (pintype "passive"))
      (node (ref "Q27") (pin "4") (pinfunction "D_4") (pintype "passive"))
    )
    (net (code "103") (name "Net-(Q27-G)") (class "Default")
      (node (ref "Q27") (pin "1") (pinfunction "G_1") (pintype "passive"))
      (node (ref "R95") (pin "1") (pinfunction "1_1") (pintype "passive"))
      (node (ref "R97") (pin "1") (pinfunction "1_1") (pintype "passive"))
    )
    (net (code "104") (name "Net-(Q29-D)") (class "Default")
      (node (ref "J15") (pin "1") (pinfunction "1_1") (pintype "passive"))
      (node (ref "Q29") (pin "4") (pinfunction "D_4") (pintype "passive"))
    )
    (net (code "105") (name "Net-(Q29-G)") (class "Default")
      (node (ref "Q29") (pin "1") (pinfunction "G_1") (pintype "passive"))
      (node (ref "R101") (pin "1") (pinfunction "1_1") (pintype "passive"))
      (node (ref "R99") (pin "1") (pinfunction "1_1") (pintype "passive"))
    )
    (net (code "106") (name "Net-(Q31-D)") (class "Default")
      (node (ref "J15") (pin "2") (pinfunction "2_2") (pintype "passive"))
      (node (ref "Q31") (pin "4") (pinfunction "D_4") (pintype "passive"))
    )
    (net (code "107") (name "Net-(Q31-G)") (class "Default")
      (node (ref "Q31") (pin "1") (pinfunction "G_1") (pintype "passive"))
      (node (ref "R103") (pin "1") (pinfunction "1_1") (pintype "passive"))
      (node (ref "R106") (pin "1") (pinfunction "1_1") (pintype "passive"))
    )
    (net (code "108") (name "Net-(R14-Pad2)") (class "Default")
      (node (ref "R14") (pin "2") (pinfunction "2_2") (pintype "passive"))
      (node (ref "led1") (pin "1") (pinfunction "1_1") (pintype "passive"))
    )
    (net (code "109") (name "Net-(R15-Pad2)") (class "Default")
      (node (ref "R15") (pin "2") (pinfunction "2_2") (pintype "passive"))
      (node (ref "led2") (pin "1") (pinfunction "1_1") (pintype "passive"))
    )
    (net (code "110") (name "Net-(R16-Pad2)") (class "Default")
      (node (ref "R16") (pin "2") (pinfunction "2_2") (pintype "passive"))
      (node (ref "led3") (pin "1") (pinfunction "1_1") (pintype "passive"))
    )
    (net (code "111") (name "Net-(R17-Pad2)") (class "Default")
      (node (ref "R17") (pin "2") (pinfunction "2_2") (pintype "passive"))
      (node (ref "led4") (pin "1") (pinfunction "1_1") (pintype "passive"))
    )
    (net (code "112") (name "Net-(R18-Pad2)") (class "Default")
      (node (ref "R18") (pin "2") (pinfunction "2_2") (pintype "passive"))
      (node (ref "led5") (pin "1") (pinfunction "1_1") (pintype "passive"))
    )
    (net (code "113") (name "Net-(R19-Pad2)") (class "Default")
      (node (ref "R19") (pin "2") (pinfunction "2_2") (pintype "passive"))
      (node (ref "led6") (pin "1") (pinfunction "1_1") (pintype "passive"))
    )
    (net (code "114") (name "Net-(R20-Pad2)") (class "Default")
      (node (ref "R20") (pin "2") (pinfunction "2_2") (pintype "passive"))
      (node (ref "led7") (pin "1") (pinfunction "1_1") (pintype "passive"))
    )
    (net (code "115") (name "Net-(R21-Pad2)") (class "Default")
      (node (ref "R21") (pin "2") (pinfunction "2_2") (pintype "passive"))
      (node (ref "led8") (pin "1") (pinfunction "1_1") (pintype "passive"))
    )
    (net (code "116") (name "Net-(R23-Pad2)") (class "Default")
      (node (ref "R23") (pin "2") (pinfunction "2_2") (pintype "passive"))
      (node (ref "led9") (pin "1") (pinfunction "1_1") (pintype "passive"))
    )
    (net (code "117") (name "Net-(R24-Pad2)") (class "Default")
      (node (ref "R24") (pin "2") (pinfunction "2_2") (pintype "passive"))
      (node (ref "led10") (pin "1") (pinfunction "1_1") (pintype "passive"))
    )
    (net (code "118") (name "Net-(R25-Pad2)") (class "Default")
      (node (ref "R25") (pin "2") (pinfunction "2_2") (pintype "passive"))
      (node (ref "led11") (pin "1") (pinfunction "1_1") (pintype "passive"))
    )
    (net (code "119") (name "Net-(R26-Pad2)") (class "Default")
      (node (ref "R26") (pin "2") (pinfunction "2_2") (pintype "passive"))
      (node (ref "led12") (pin "1") (pinfunction "1_1") (pintype "passive"))
    )
    (net (code "120") (name "Net-(R27-Pad2)") (class "Default")
      (node (ref "R27") (pin "2") (pinfunction "2_2") (pintype "passive"))
      (node (ref "led13") (pin "1") (pinfunction "1_1") (pintype "passive"))
    )
    (net (code "121") (name "Net-(R28-Pad2)") (class "Default")
      (node (ref "R28") (pin "2") (pinfunction "2_2") (pintype "passive"))
      (node (ref "led14") (pin "1") (pinfunction "1_1") (pintype "passive"))
    )
    (net (code "122") (name "Net-(R29-Pad2)") (class "Default")
      (node (ref "R29") (pin "2") (pinfunction "2_2") (pintype "passive"))
      (node (ref "led15") (pin "1") (pinfunction "1_1") (pintype "passive"))
    )
    (net (code "123") (name "Net-(R30-Pad2)") (class "Default")
      (node (ref "R30") (pin "2") (pinfunction "2_2") (pintype "passive"))
      (node (ref "led16") (pin "1") (pinfunction "1_1") (pintype "passive"))
    )
    (net (code "124") (name "Net-(R71-Pad2)") (class "Default")
      (node (ref "R71") (pin "2") (pinfunction "2_2") (pintype "passive"))
      (node (ref "led17") (pin "1") (pinfunction "1_1") (pintype "passive"))
    )
    (net (code "125") (name "Net-(R72-Pad2)") (class "Default")
      (node (ref "R72") (pin "2") (pinfunction "2_2") (pintype "passive"))
      (node (ref "led18") (pin "1") (pinfunction "1_1") (pintype "passive"))
    )
    (net (code "126") (name "Net-(R73-Pad2)") (class "Default")
      (node (ref "R73") (pin "2") (pinfunction "2_2") (pintype "passive"))
      (node (ref "led19") (pin "1") (pinfunction "1_1") (pintype "passive"))
    )
    (net (code "127") (name "Net-(R74-Pad2)") (class "Default")
      (node (ref "R74") (pin "2") (pinfunction "2_2") (pintype "passive"))
      (node (ref "led20") (pin "1") (pinfunction "1_1") (pintype "passive"))
    )
    (net (code "128") (name "Net-(R75-Pad2)") (class "Default")
      (node (ref "R75") (pin "2") (pinfunction "2_2") (pintype "passive"))
      (node (ref "led21") (pin "1") (pinfunction "1_1") (pintype "passive"))
    )
    (net (code "129") (name "Net-(R76-Pad2)") (class "Default")
      (node (ref "R76") (pin "2") (pinfunction "2_2") (pintype "passive"))
      (node (ref "led22") (pin "1") (pinfunction "1_1") (pintype "passive"))
    )
    (net (code "130") (name "Net-(R77-Pad2)") (class "Default")
      (node (ref "R77") (pin "2") (pinfunction "2_2") (pintype "passive"))
      (node (ref "led23") (pin "1") (pinfunction "1_1") (pintype "passive"))
    )
    (net (code "131") (name "Net-(R78-Pad2)") (class "Default")
      (node (ref "R78") (pin "2") (pinfunction "2_2") (pintype "passive"))
      (node (ref "led24") (pin "1") (pinfunction "1_1") (pintype "passive"))
    )
    (net (code "132") (name "Net-(R85-Pad2)") (class "Default")
      (node (ref "R85") (pin "2") (pinfunction "2_2") (pintype "passive"))
      (node (ref "led30") (pin "1") (pinfunction "1_1") (pintype "passive"))
    )
    (net (code "133") (name "Net-(R86-Pad2)") (class "Default")
      (node (ref "R86") (pin "2") (pinfunction "2_2") (pintype "passive"))
      (node (ref "led31") (pin "1") (pinfunction "1_1") (pintype "passive"))
    )
    (net (code "134") (name "Net-(R87-Pad2)") (class "Default")
      (node (ref "R87") (pin "2") (pinfunction "2_2") (pintype "passive"))
      (node (ref "led32") (pin "1") (pinfunction "1_1") (pintype "passive"))
    )
    (net (code "135") (name "Net-(R108-Pad1)") (class "Default")
      (node (ref "R108") (pin "1") (pinfunction "1_1") (pintype "passive"))
      (node (ref "led33") (pin "2") (pinfunction "2_2") (pintype "passive"))
    )
    (net (code "136") (name "Net-(U1-DATAO)") (class "Default")
      (node (ref "U1") (pin "9") (pinfunction "DATAO_9") (pintype "output"))
      (node (ref "U2") (pin "14") (pinfunction "DS_14") (pintype "input"))
    )
    (net (code "137") (name "Net-(U2-DATAO)") (class "Default")
      (node (ref "U2") (pin "9") (pinfunction "DATAO_9") (pintype "output"))
      (node (ref "U3") (pin "14") (pinfunction "DS_14") (pintype "input"))
    )
    (net (code "138") (name "Net-(U3-DATAO)") (class "Default")
      (node (ref "U3") (pin "9") (pinfunction "DATAO_9") (pintype "output"))
      (node (ref "U4") (pin "14") (pinfunction "DS_14") (pintype "input"))
    )
    (net (code "139") (name "Net-(U5-Vin)") (class "Default")
      (node (ref "C13") (pin "2") (pinfunction "2_2") (pintype "passive"))
      (node (ref "F1") (pin "1") (pinfunction "1_1") (pintype "passive"))
      (node (ref "U5") (pin "1") (pinfunction "Vin_1") (pintype "passive"))
    )
    (net (code "140") (name "Vin") (class "Default")
      (node (ref "D1") (pin "2") (pinfunction "K_2") (pintype "passive"))
      (node (ref "F1") (pin "2") (pinfunction "2_2") (pintype "passive"))
    )
    (net (code "141") (name "unconnected-(ESP1-CS0-Pad9)") (class "Default")
      (node (ref "ESP1") (pin "9") (pinfunction "CS0_9") (pintype "input"))
    )
    (net (code "142") (name "unconnected-(ESP1-IO9-Pad11)") (class "Default")
      (node (ref "ESP1") (pin "11") (pinfunction "IO9_11") (pintype "bidirectional"))
    )
    (net (code "143") (name "unconnected-(ESP1-IO10-Pad12)") (class "Default")
      (node (ref "ESP1") (pin "12") (pinfunction "IO10_12") (pintype "bidirectional"))
    )
    (net (code "144") (name "unconnected-(ESP1-MISO-Pad10)") (class "Default")
      (node (ref "ESP1") (pin "10") (pinfunction "MISO_10") (pintype "bidirectional"))
    )
    (net (code "145") (name "unconnected-(ESP1-MOSI-Pad13)") (class "Default")
      (node (ref "ESP1") (pin "13") (pinfunction "MOSI_13") (pintype "bidirectional"))
    )
    (net (code "146") (name "unconnected-(ESP1-SCLK-Pad14)") (class "Default")
      (node (ref "ESP1") (pin "14") (pinfunction "SCLK_14") (pintype "input"))
    )
    (net (code "147") (name "unconnected-(J12-Pad2)") (class "Default")
      (node (ref "J12") (pin "2") (pinfunction "2_2") (pintype "passive"))
    )
    (net (code "148") (name "unconnected-(SW1-Pad3)") (class "Default")
      (node (ref "SW1") (pin "3") (pinfunction "3_3") (pintype "passive"))
    )
    (net (code "149") (name "unconnected-(SW1-Pad4)") (class "Default")
      (node (ref "SW1") (pin "4") (pinfunction "4_4") (pintype "passive"))
    )
    (net (code "150") (name "unconnected-(SW2-Pad3)") (class "Default")
      (node (ref "SW2") (pin "3") (pinfunction "3_3") (pintype "passive"))
    )
    (net (code "151") (name "unconnected-(SW2-Pad4)") (class "Default")
      (node (ref "SW2") (pin "4") (pinfunction "4_4") (pintype "passive"))
    )
    (net (code "152") (name "unconnected-(U4-DATAO-Pad9)") (class "Default")
      (node (ref "U4") (pin "9") (pinfunction "DATAO_9") (pintype "output"))
    )
  )
)
